# classix.net
KiCad netlist of a schematic drawn in EAGLE
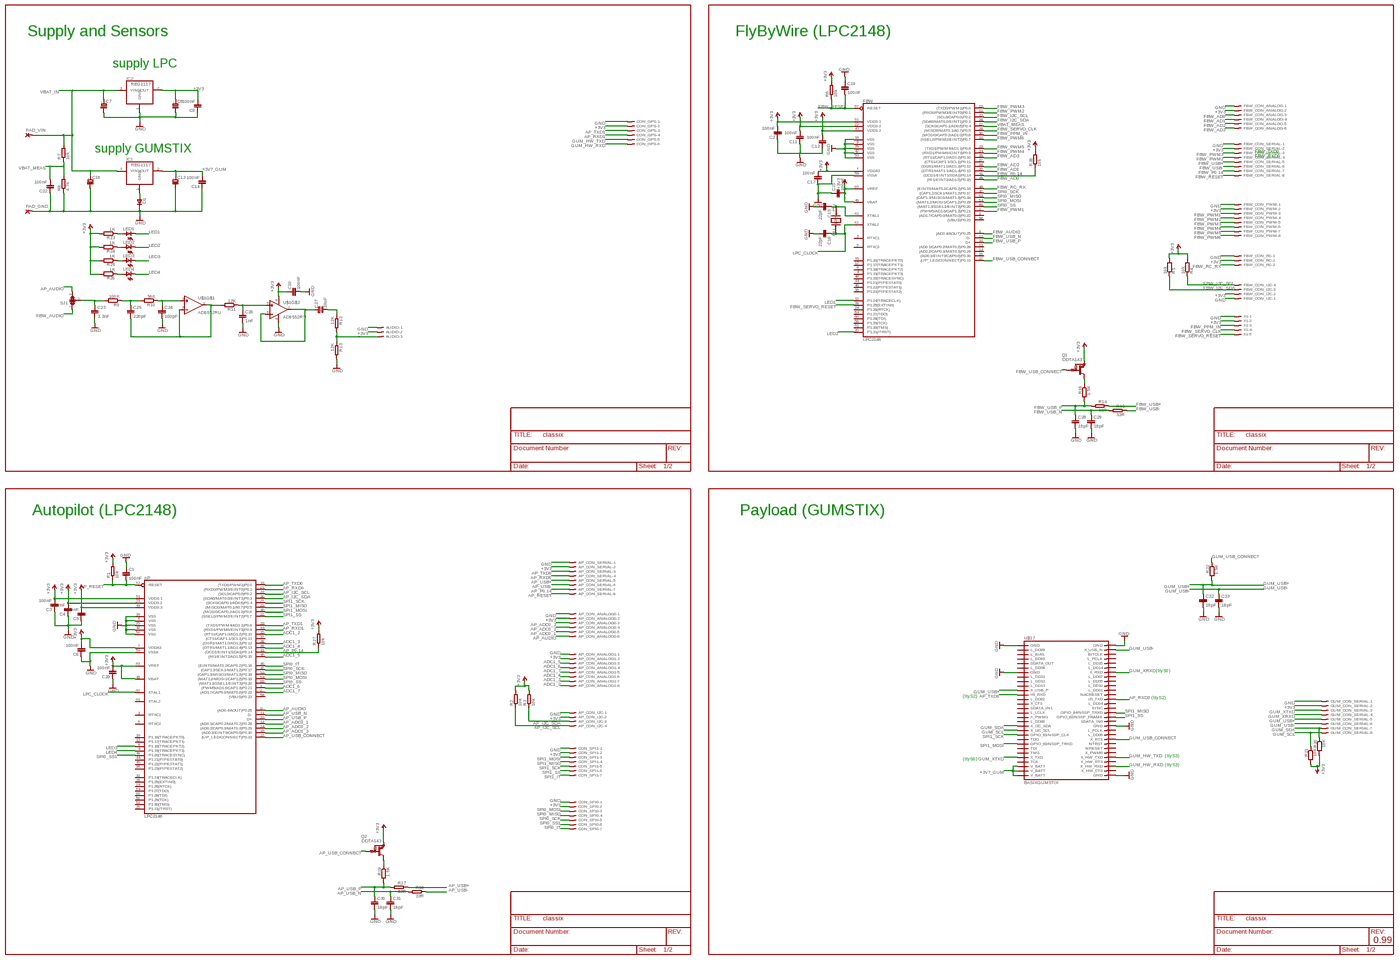
[diagram p0: schematic, sheet 1, overview]
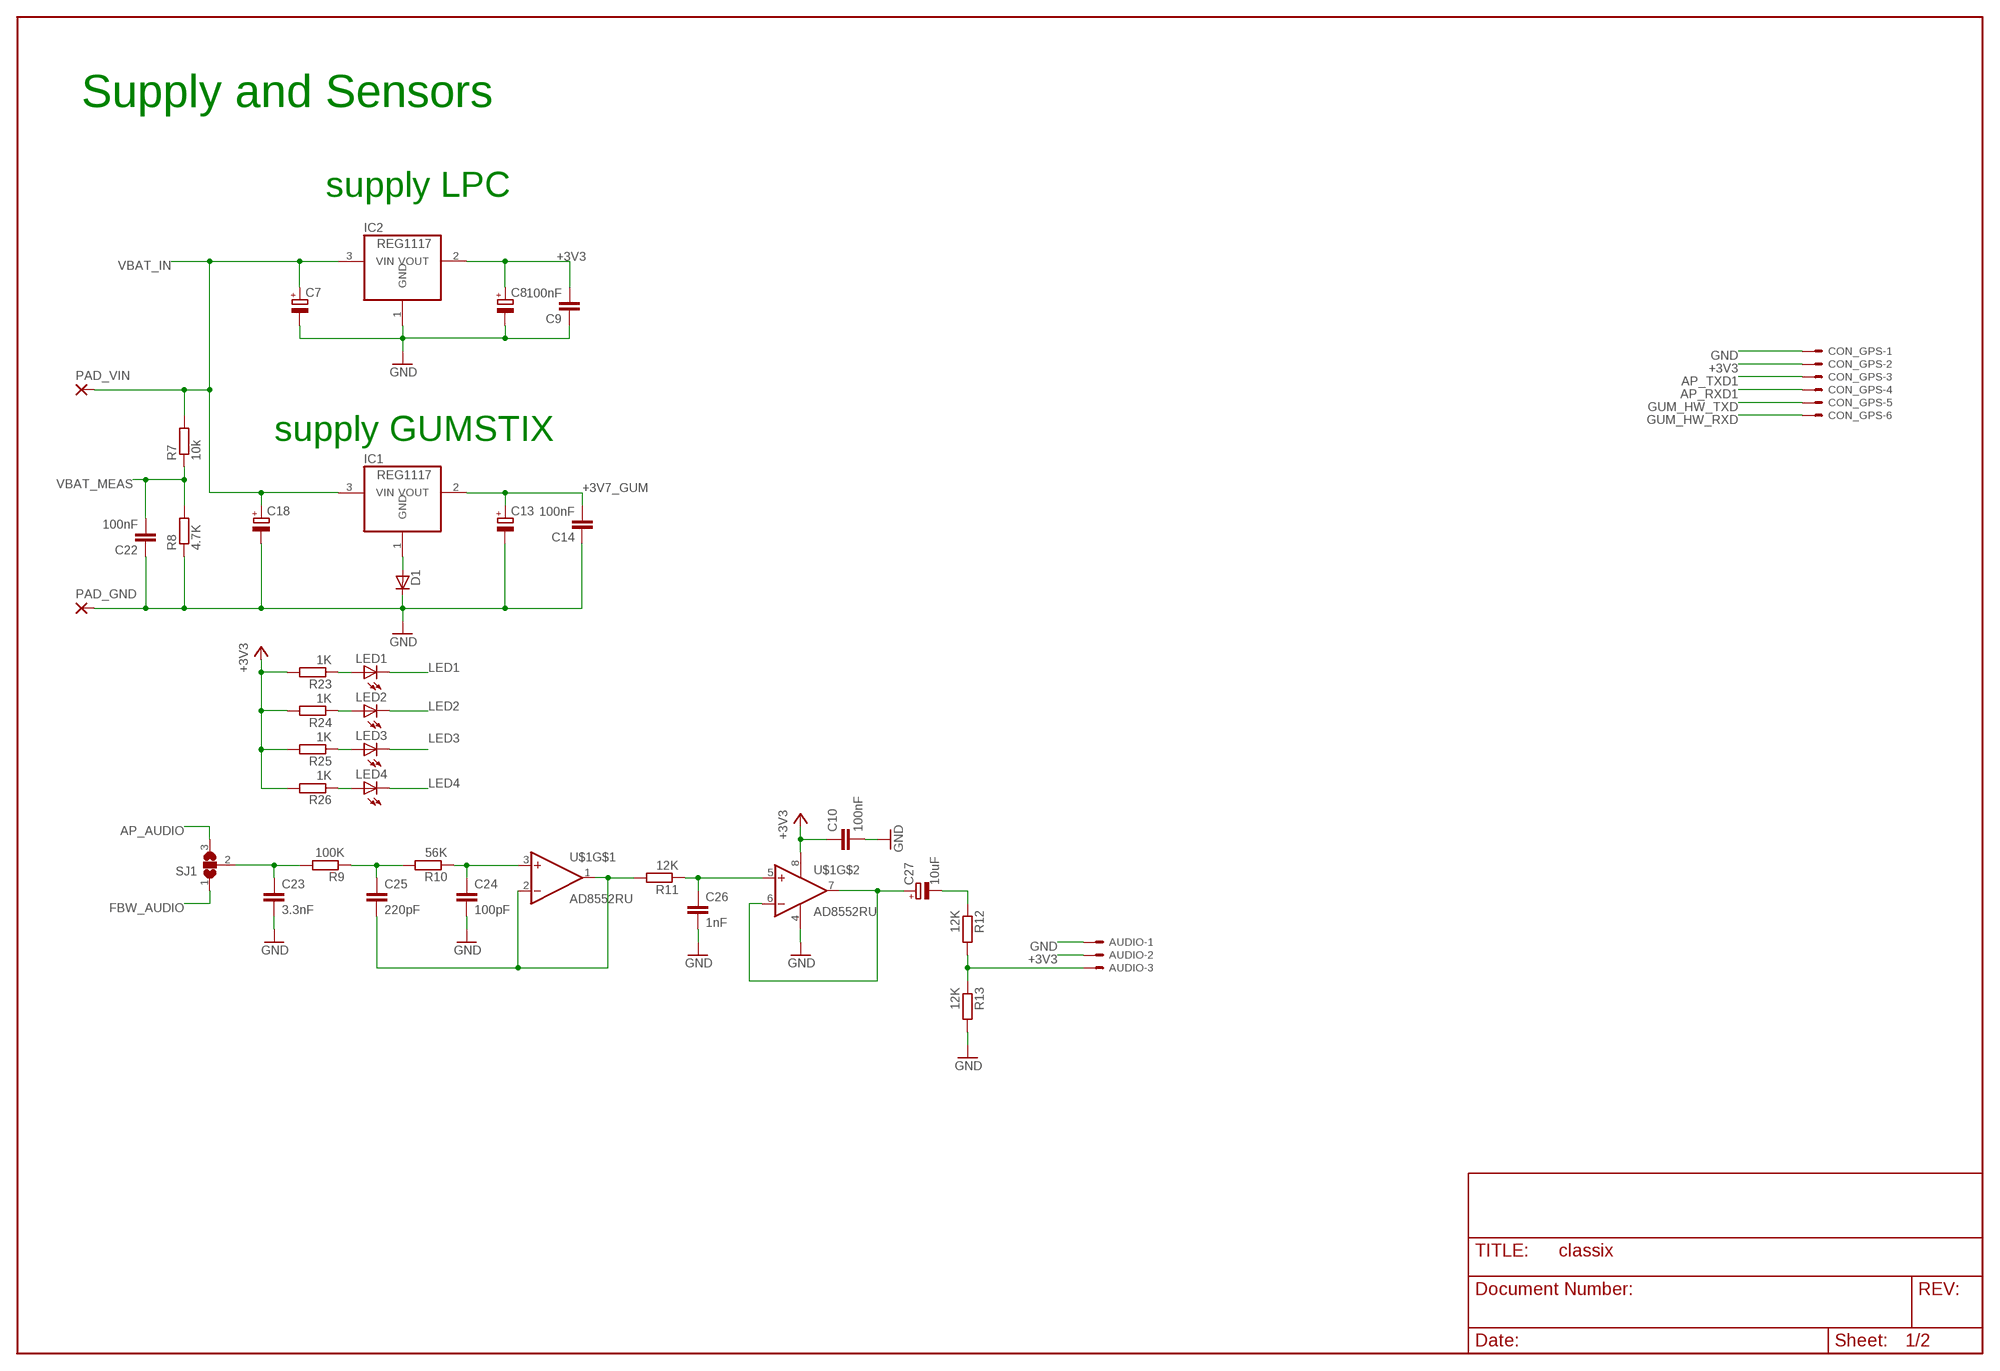
[diagram p1: schematic, sheet 1, part 1 of 4]
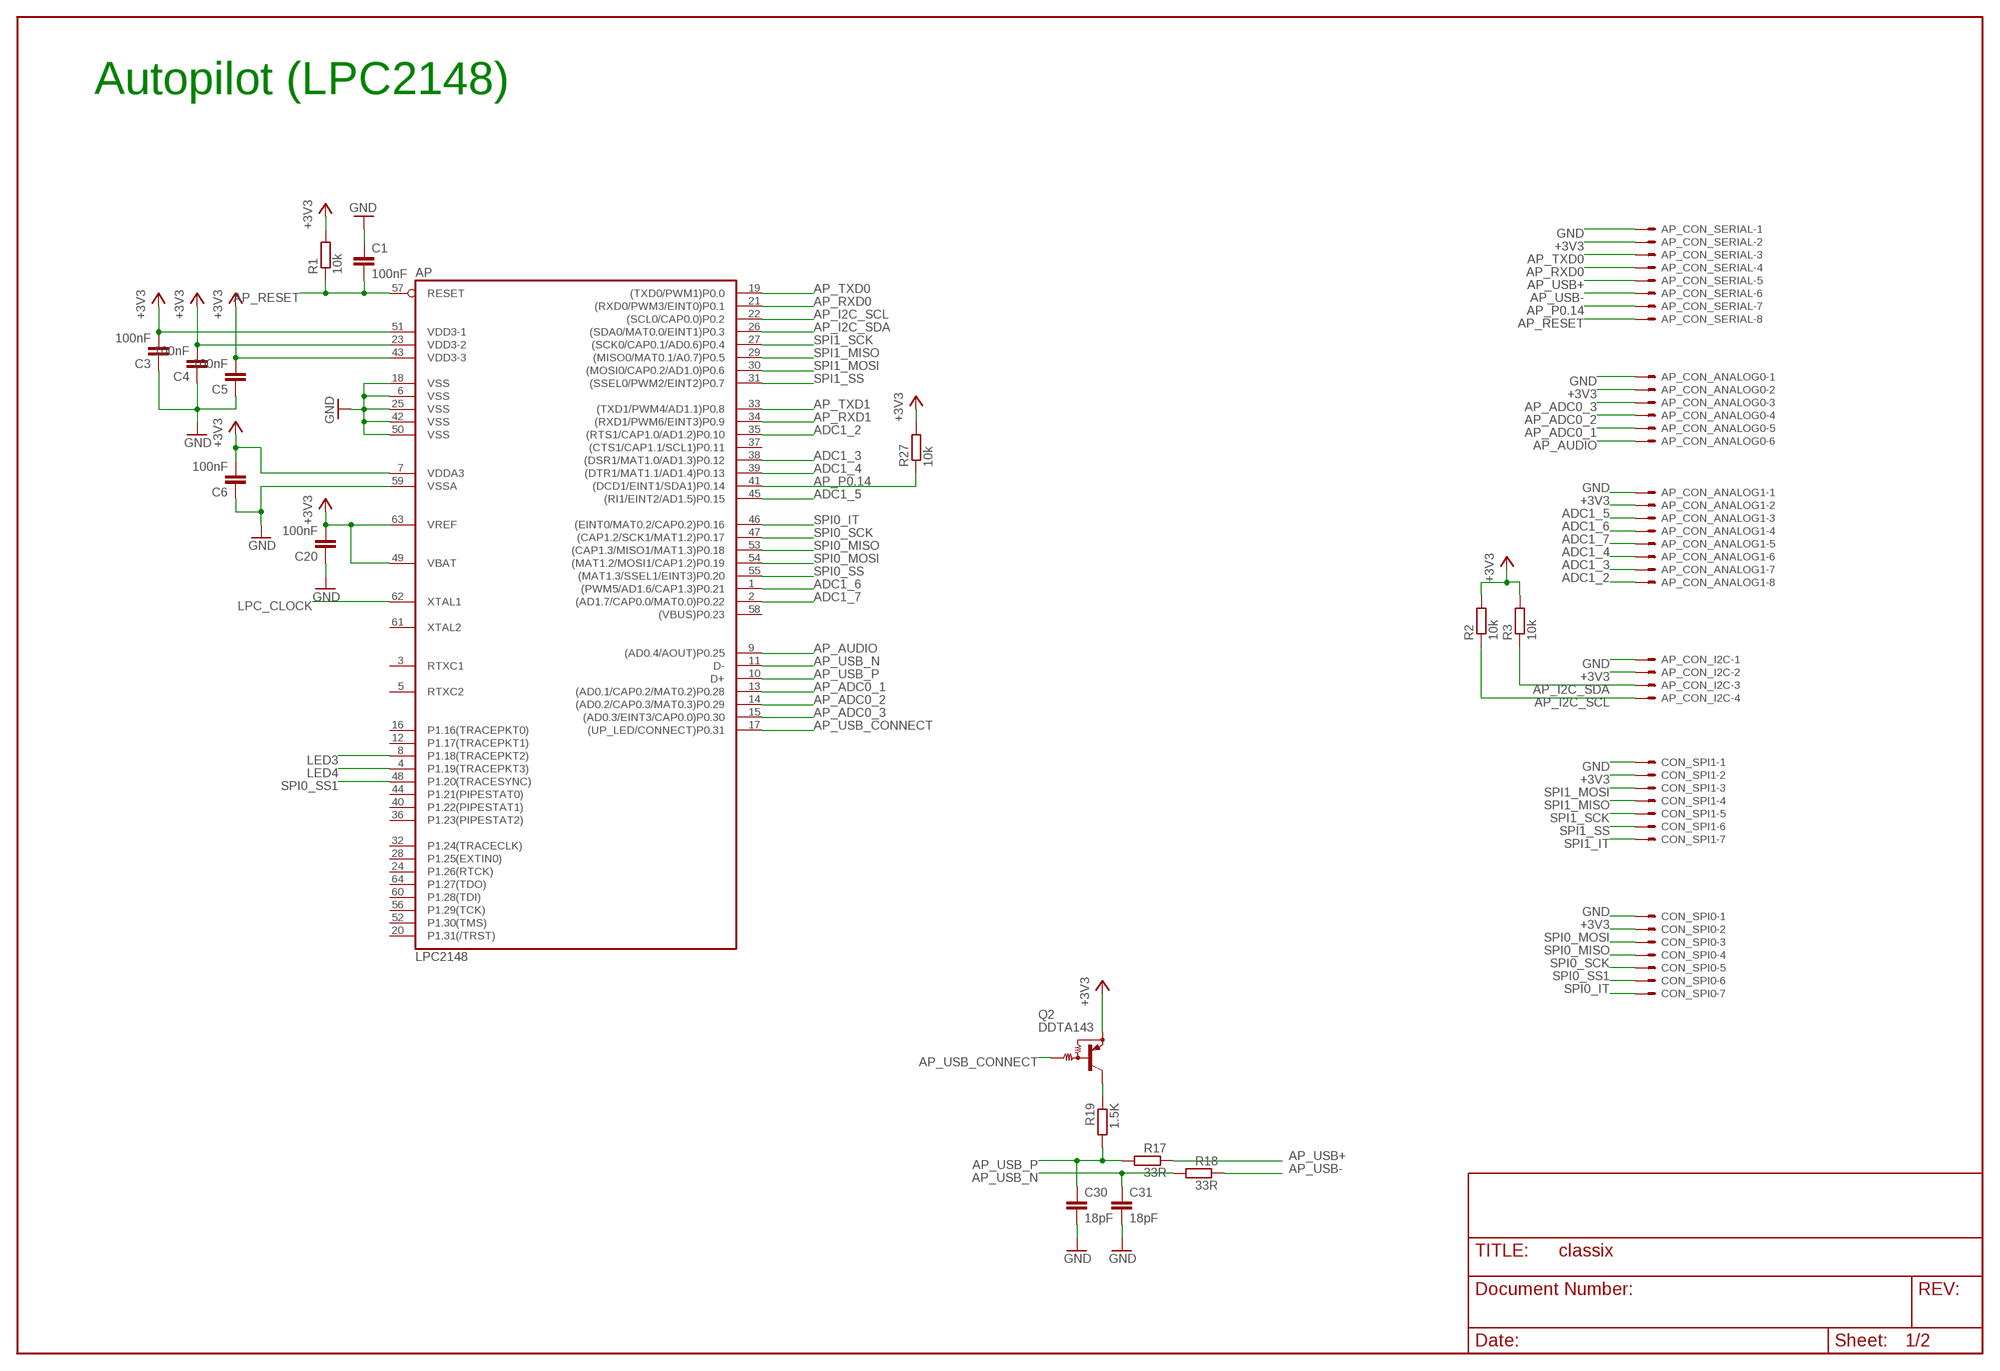
[diagram p2: schematic, sheet 1, part 2 of 4]
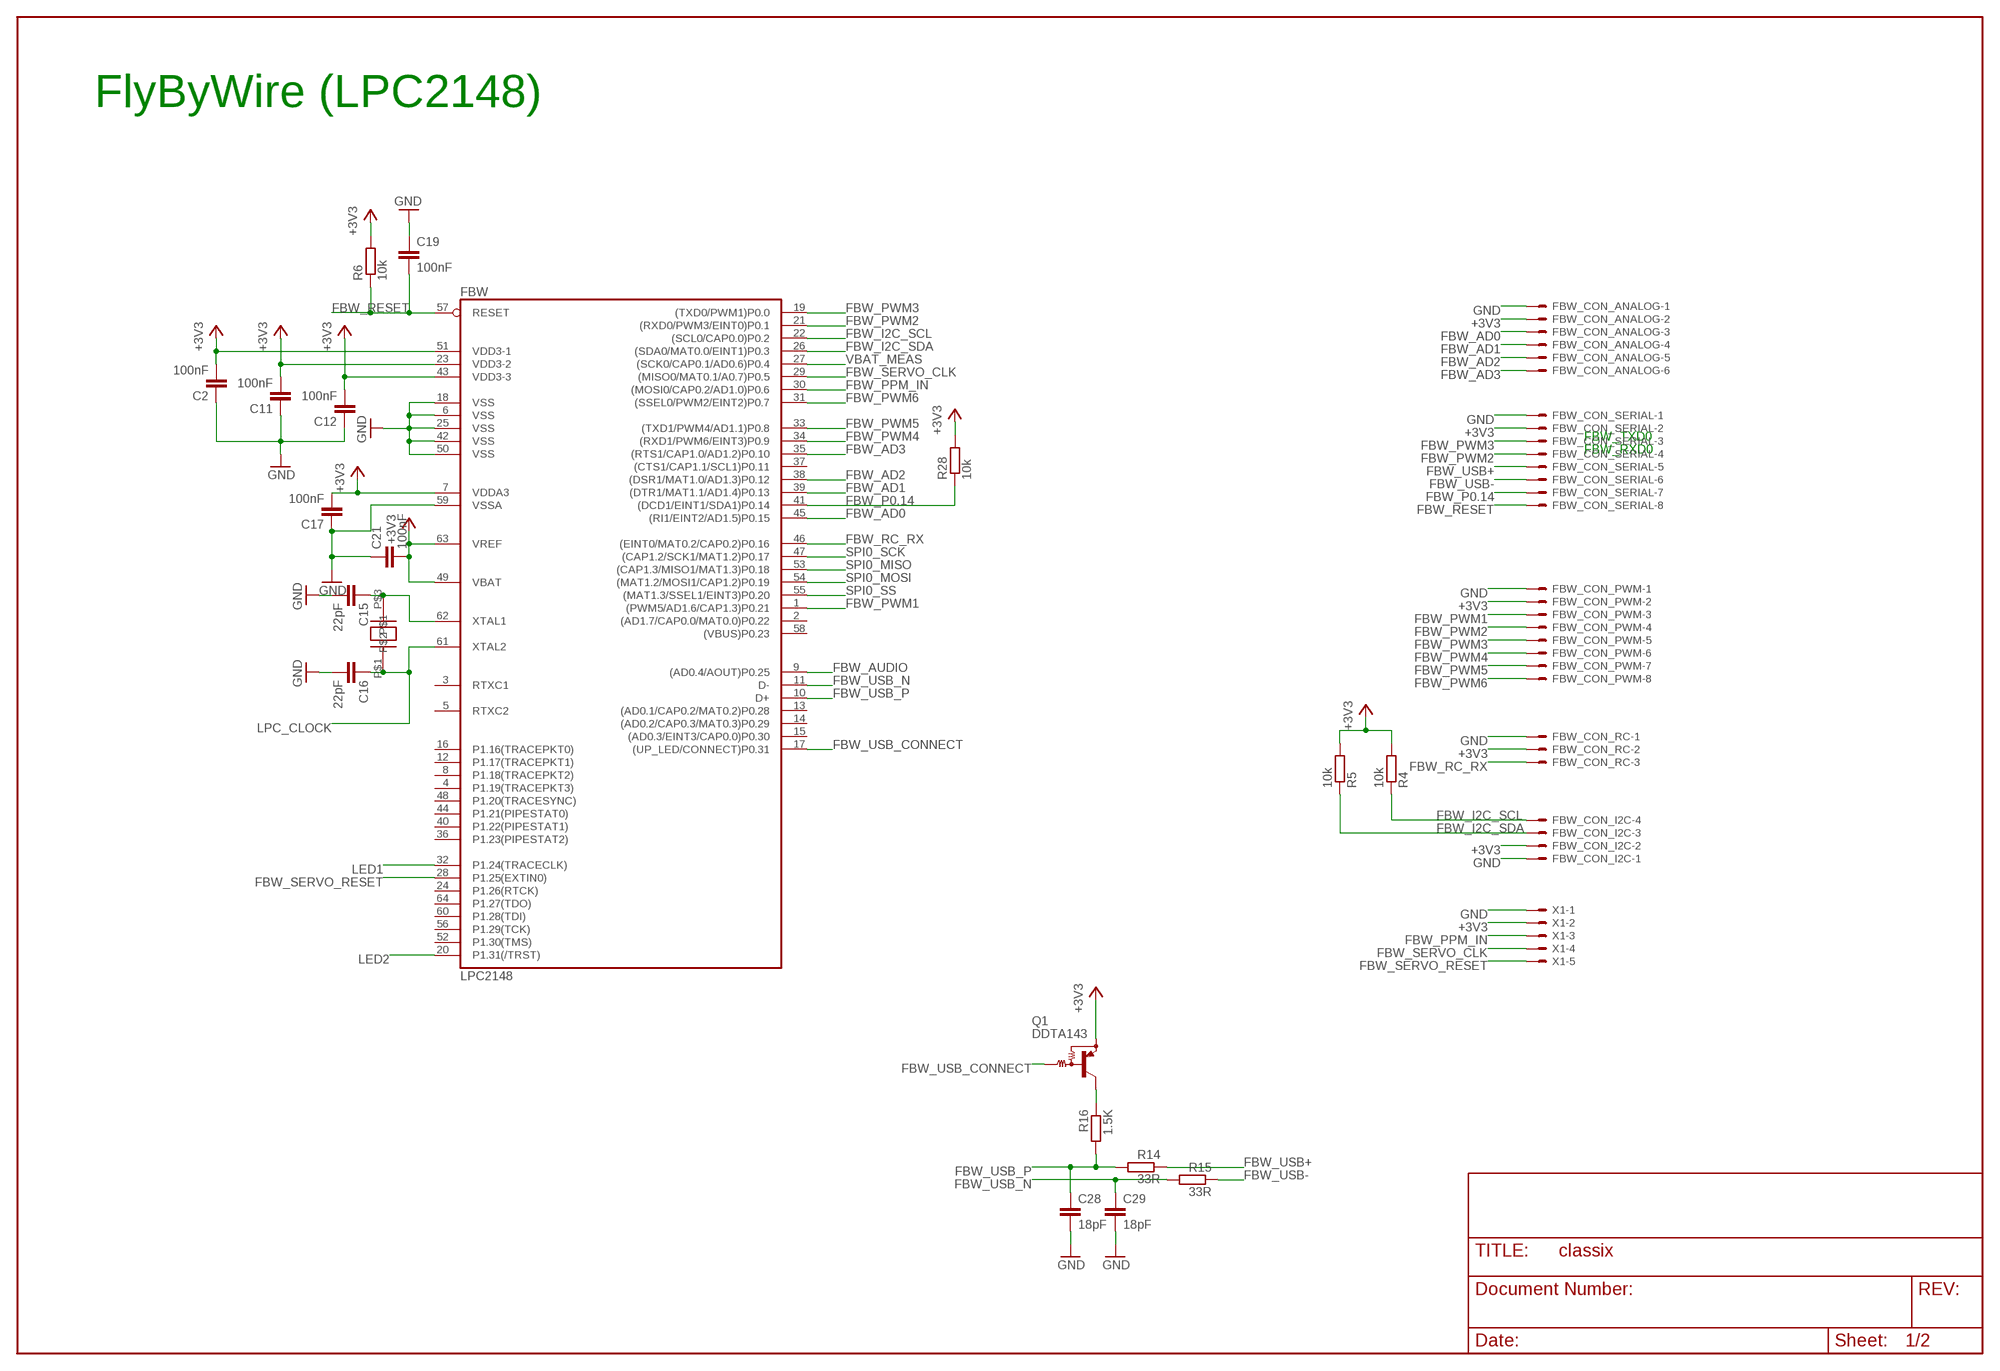
[diagram p3: schematic, sheet 1, part 3 of 4]
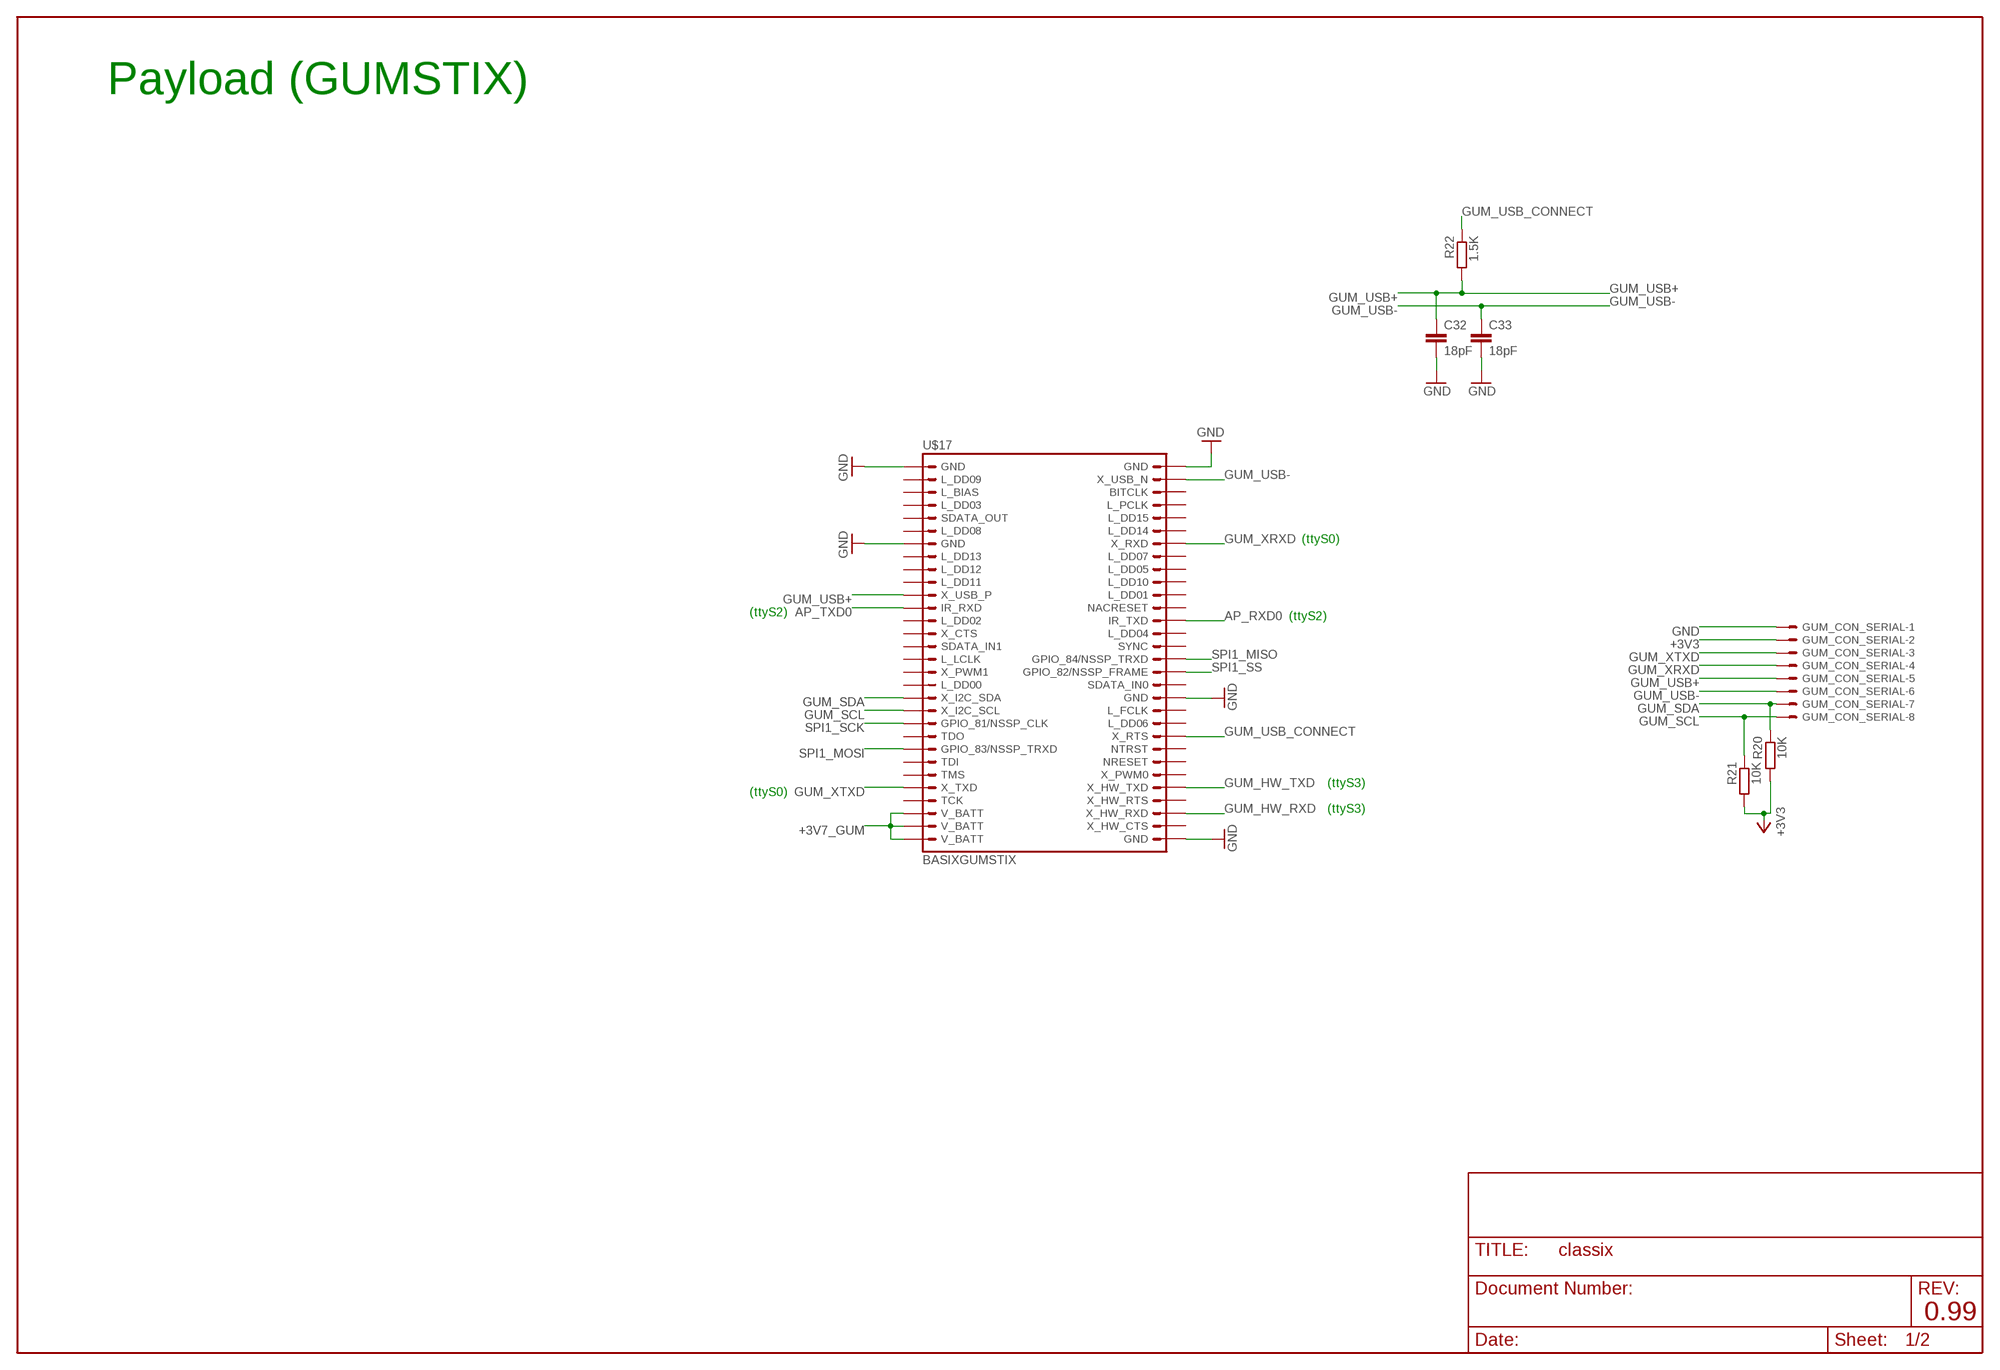
[diagram p4: schematic, sheet 1, part 4 of 4]

(export (version "E")
  (design (tool "Eeschema 10.0.6"))
  (components
    (comp (ref "AP")
      (value "LPC2148")
      (footprint "eagle-import:SQFP-S-10X10-64")
      (libsource (lib "eagle-import") (part "LPC2148"))
    )
    (comp (ref "AP_CON_ANALOG0")
      (value "53047-06")
      (footprint "eagle-import:53047-06")
      (libsource (lib "eagle-import") (part "53?-06047"))
    )
    (comp (ref "AP_CON_ANALOG1")
      (value "53047-08")
      (footprint "eagle-import:53047-08")
      (libsource (lib "eagle-import") (part "53?-08047"))
    )
    (comp (ref "AP_CON_I2C")
      (value "53047-04")
      (footprint "eagle-import:53047-04")
      (libsource (lib "eagle-import") (part "53?-04047"))
    )
    (comp (ref "AP_CON_SERIAL")
      (value "53047-08")
      (footprint "eagle-import:53047-08")
      (libsource (lib "eagle-import") (part "53?-08047"))
    )
    (comp (ref "AUDIO")
      (value "53047-03")
      (footprint "eagle-import:53047-03")
      (libsource (lib "eagle-import") (part "53?-03047"))
    )
    (comp (ref "C1")
      (value "100nF")
      (footprint "eagle-import:C0603")
      (libsource (lib "eagle-import") (part "C-EUC0603"))
    )
    (comp (ref "C2")
      (value "100nF")
      (footprint "eagle-import:C0603")
      (libsource (lib "eagle-import") (part "C-EUC0603"))
    )
    (comp (ref "C3")
      (value "100nF")
      (footprint "eagle-import:C0603")
      (libsource (lib "eagle-import") (part "C-EUC0603"))
    )
    (comp (ref "C4")
      (value "100nF")
      (footprint "eagle-import:C0603")
      (libsource (lib "eagle-import") (part "C-EUC0603"))
    )
    (comp (ref "C5")
      (value "100nF")
      (footprint "eagle-import:C0603")
      (libsource (lib "eagle-import") (part "C-EUC0603"))
    )
    (comp (ref "C6")
      (value "100nF")
      (footprint "eagle-import:C0603")
      (libsource (lib "eagle-import") (part "C-EUC0603"))
    )
    (comp (ref "C7")
      (value "CPOL-EUA/3216-18R")
      (footprint "eagle-import:A_3216-18R")
      (libsource (lib "eagle-import") (part "CPOL-EUA/3216-18R"))
    )
    (comp (ref "C8")
      (value "CPOL-EUB/3528-21R")
      (footprint "eagle-import:B_3528-21R")
      (libsource (lib "eagle-import") (part "CPOL-EUB/3528-21R"))
    )
    (comp (ref "C9")
      (value "100nF")
      (footprint "eagle-import:C0603")
      (libsource (lib "eagle-import") (part "C-EUC0603"))
    )
    (comp (ref "C10")
      (value "100nF")
      (footprint "eagle-import:C0603")
      (libsource (lib "eagle-import") (part "C-EUC0603"))
    )
    (comp (ref "C11")
      (value "100nF")
      (footprint "eagle-import:C0603")
      (libsource (lib "eagle-import") (part "C-EUC0603"))
    )
    (comp (ref "C12")
      (value "100nF")
      (footprint "eagle-import:C0603")
      (libsource (lib "eagle-import") (part "C-EUC0603"))
    )
    (comp (ref "C13")
      (value "CPOL-EUB/3528-21R")
      (footprint "eagle-import:B_3528-21R")
      (libsource (lib "eagle-import") (part "CPOL-EUB/3528-21R"))
    )
    (comp (ref "C14")
      (value "100nF")
      (footprint "eagle-import:C0603")
      (libsource (lib "eagle-import") (part "C-EUC0603"))
    )
    (comp (ref "C15")
      (value "22pF")
      (footprint "eagle-import:C0603")
      (libsource (lib "eagle-import") (part "C-EUC0603"))
    )
    (comp (ref "C16")
      (value "22pF")
      (footprint "eagle-import:C0603")
      (libsource (lib "eagle-import") (part "C-EUC0603"))
    )
    (comp (ref "C17")
      (value "100nF")
      (footprint "eagle-import:C0603")
      (libsource (lib "eagle-import") (part "C-EUC0603"))
    )
    (comp (ref "C18")
      (value "CPOL-EUA/3216-18R")
      (footprint "eagle-import:A_3216-18R")
      (libsource (lib "eagle-import") (part "CPOL-EUA/3216-18R"))
    )
    (comp (ref "C19")
      (value "100nF")
      (footprint "eagle-import:C0603")
      (libsource (lib "eagle-import") (part "C-EUC0603"))
    )
    (comp (ref "C20")
      (value "100nF")
      (footprint "eagle-import:C0603")
      (libsource (lib "eagle-import") (part "C-EUC0603"))
    )
    (comp (ref "C21")
      (value "100nF")
      (footprint "eagle-import:C0603")
      (libsource (lib "eagle-import") (part "C-EUC0603"))
    )
    (comp (ref "C22")
      (value "100nF")
      (footprint "eagle-import:C0603")
      (libsource (lib "eagle-import") (part "C-EUC0603"))
    )
    (comp (ref "C23")
      (value "3.3nF")
      (footprint "eagle-import:C0603")
      (libsource (lib "eagle-import") (part "C-EUC0603"))
    )
    (comp (ref "C24")
      (value "100pF")
      (footprint "eagle-import:C0603")
      (libsource (lib "eagle-import") (part "C-EUC0603"))
    )
    (comp (ref "C25")
      (value "220pF")
      (footprint "eagle-import:C0603")
      (libsource (lib "eagle-import") (part "C-EUC0603"))
    )
    (comp (ref "C26")
      (value "1nF")
      (footprint "eagle-import:C0603")
      (libsource (lib "eagle-import") (part "C-EUC0603"))
    )
    (comp (ref "C27")
      (value "10uF")
      (footprint "eagle-import:A_3216-18R")
      (libsource (lib "eagle-import") (part "CPOL-EUA/3216-18R"))
    )
    (comp (ref "C28")
      (value "18pF")
      (footprint "eagle-import:C0603")
      (libsource (lib "eagle-import") (part "C-EUC0603"))
    )
    (comp (ref "C29")
      (value "18pF")
      (footprint "eagle-import:C0603")
      (libsource (lib "eagle-import") (part "C-EUC0603"))
    )
    (comp (ref "C30")
      (value "18pF")
      (footprint "eagle-import:C0603")
      (libsource (lib "eagle-import") (part "C-EUC0603"))
    )
    (comp (ref "C31")
      (value "18pF")
      (footprint "eagle-import:C0603")
      (libsource (lib "eagle-import") (part "C-EUC0603"))
    )
    (comp (ref "C32")
      (value "18pF")
      (footprint "eagle-import:C0603")
      (libsource (lib "eagle-import") (part "C-EUC0603"))
    )
    (comp (ref "C33")
      (value "18pF")
      (footprint "eagle-import:C0603")
      (libsource (lib "eagle-import") (part "C-EUC0603"))
    )
    (comp (ref "CON_GPS")
      (value "53047-06")
      (footprint "eagle-import:53047-06")
      (libsource (lib "eagle-import") (part "53?-06047"))
    )
    (comp (ref "CON_SPI0")
      (value "53047-07")
      (footprint "eagle-import:53047-07")
      (libsource (lib "eagle-import") (part "53?-07047"))
    )
    (comp (ref "CON_SPI1")
      (value "53047-07")
      (footprint "eagle-import:53047-07")
      (libsource (lib "eagle-import") (part "53?-07047"))
    )
    (comp (ref "D1")
      (value "D-SOD-80")
      (footprint "eagle-import:SOD80")
      (libsource (lib "eagle-import") (part "D-SOD-80"))
    )
    (comp (ref "FBW")
      (value "LPC2148")
      (footprint "eagle-import:SQFP-S-10X10-64")
      (libsource (lib "eagle-import") (part "LPC2148"))
    )
    (comp (ref "FBW_CON_ANALOG")
      (value "53047-06")
      (footprint "eagle-import:53047-06")
      (libsource (lib "eagle-import") (part "53?-06047"))
    )
    (comp (ref "FBW_CON_I2C")
      (value "53047-04")
      (footprint "eagle-import:53047-04")
      (libsource (lib "eagle-import") (part "53?-04047"))
    )
    (comp (ref "FBW_CON_PWM")
      (value "53047-08")
      (footprint "eagle-import:53047-08")
      (libsource (lib "eagle-import") (part "53?-08047"))
    )
    (comp (ref "FBW_CON_RC")
      (value "53047-03")
      (footprint "eagle-import:53047-03")
      (libsource (lib "eagle-import") (part "53?-03047"))
    )
    (comp (ref "FBW_CON_SERIAL")
      (value "53047-08")
      (footprint "eagle-import:53047-08")
      (libsource (lib "eagle-import") (part "53?-08047"))
    )
    (comp (ref "GUM_CON_SERIAL")
      (value "53047-08")
      (footprint "eagle-import:53047-08")
      (libsource (lib "eagle-import") (part "53?-08047"))
    )
    (comp (ref "IC1")
      (value "REG1117")
      (footprint "eagle-import:SOT223")
      (libsource (lib "eagle-import") (part "REG1117"))
    )
    (comp (ref "IC2")
      (value "REG1117")
      (footprint "eagle-import:SOT223")
      (libsource (lib "eagle-import") (part "REG1117"))
    )
    (comp (ref "LED1")
      (value "LEDCHIP-LED0805")
      (footprint "eagle-import:CHIP-LED0805")
      (libsource (lib "eagle-import") (part "LEDCHIP-LED0805"))
    )
    (comp (ref "LED2")
      (value "LEDCHIP-LED0805")
      (footprint "eagle-import:CHIP-LED0805")
      (libsource (lib "eagle-import") (part "LEDCHIP-LED0805"))
    )
    (comp (ref "LED3")
      (value "LEDCHIP-LED0805")
      (footprint "eagle-import:CHIP-LED0805")
      (libsource (lib "eagle-import") (part "LEDCHIP-LED0805"))
    )
    (comp (ref "LED4")
      (value "LEDCHIP-LED0805")
      (footprint "eagle-import:CHIP-LED0805")
      (libsource (lib "eagle-import") (part "LEDCHIP-LED0805"))
    )
    (comp (ref "PAD_GND")
      (value "SMD5")
      (footprint "eagle-import:SMD5")
      (libsource (lib "eagle-import") (part "SMD5"))
    )
    (comp (ref "PAD_VIN")
      (value "SMD5")
      (footprint "eagle-import:SMD5")
      (libsource (lib "eagle-import") (part "SMD5"))
    )
    (comp (ref "Q1")
      (value "DDTA143")
      (footprint "eagle-import:SC59-BEC")
      (libsource (lib "eagle-import") (part "MUN2111T1"))
    )
    (comp (ref "Q2")
      (value "DDTA143")
      (footprint "eagle-import:SC59-BEC")
      (libsource (lib "eagle-import") (part "MUN2111T1"))
    )
    (comp (ref "R1")
      (value "10k")
      (footprint "eagle-import:R0603")
      (libsource (lib "eagle-import") (part "R-EU_R0603"))
    )
    (comp (ref "R2")
      (value "10k")
      (footprint "eagle-import:R0603")
      (libsource (lib "eagle-import") (part "R-EU_R0603"))
    )
    (comp (ref "R3")
      (value "10k")
      (footprint "eagle-import:R0603")
      (libsource (lib "eagle-import") (part "R-EU_R0603"))
    )
    (comp (ref "R4")
      (value "10k")
      (footprint "eagle-import:R0603")
      (libsource (lib "eagle-import") (part "R-EU_R0603"))
    )
    (comp (ref "R5")
      (value "10k")
      (footprint "eagle-import:R0603")
      (libsource (lib "eagle-import") (part "R-EU_R0603"))
    )
    (comp (ref "R6")
      (value "10k")
      (footprint "eagle-import:R0603")
      (libsource (lib "eagle-import") (part "R-EU_R0603"))
    )
    (comp (ref "R7")
      (value "10k")
      (footprint "eagle-import:R0603")
      (libsource (lib "eagle-import") (part "R-EU_R0603"))
    )
    (comp (ref "R8")
      (value "4.7K")
      (footprint "eagle-import:R0603")
      (libsource (lib "eagle-import") (part "R-EU_R0603"))
    )
    (comp (ref "R9")
      (value "100K")
      (footprint "eagle-import:R0603")
      (libsource (lib "eagle-import") (part "R-EU_R0603"))
    )
    (comp (ref "R10")
      (value "56K")
      (footprint "eagle-import:R0603")
      (libsource (lib "eagle-import") (part "R-EU_R0603"))
    )
    (comp (ref "R11")
      (value "12K")
      (footprint "eagle-import:R0603")
      (libsource (lib "eagle-import") (part "R-EU_R0603"))
    )
    (comp (ref "R12")
      (value "12K")
      (footprint "eagle-import:R0603")
      (libsource (lib "eagle-import") (part "R-EU_R0603"))
    )
    (comp (ref "R13")
      (value "12K")
      (footprint "eagle-import:R0603")
      (libsource (lib "eagle-import") (part "R-EU_R0603"))
    )
    (comp (ref "R14")
      (value "33R")
      (footprint "eagle-import:R0603")
      (libsource (lib "eagle-import") (part "R-EU_R0603"))
    )
    (comp (ref "R15")
      (value "33R")
      (footprint "eagle-import:R0603")
      (libsource (lib "eagle-import") (part "R-EU_R0603"))
    )
    (comp (ref "R16")
      (value "1.5K")
      (footprint "eagle-import:R0603")
      (libsource (lib "eagle-import") (part "R-EU_R0603"))
    )
    (comp (ref "R17")
      (value "33R")
      (footprint "eagle-import:R0603")
      (libsource (lib "eagle-import") (part "R-EU_R0603"))
    )
    (comp (ref "R18")
      (value "33R")
      (footprint "eagle-import:R0603")
      (libsource (lib "eagle-import") (part "R-EU_R0603"))
    )
    (comp (ref "R19")
      (value "1.5K")
      (footprint "eagle-import:R0603")
      (libsource (lib "eagle-import") (part "R-EU_R0603"))
    )
    (comp (ref "R20")
      (value "10K")
      (footprint "eagle-import:R0603")
      (libsource (lib "eagle-import") (part "R-EU_R0603"))
    )
    (comp (ref "R21")
      (value "10K")
      (footprint "eagle-import:R0603")
      (libsource (lib "eagle-import") (part "R-EU_R0603"))
    )
    (comp (ref "R22")
      (value "1.5K")
      (footprint "eagle-import:R0603")
      (libsource (lib "eagle-import") (part "R-EU_R0603"))
    )
    (comp (ref "R23")
      (value "1K")
      (footprint "eagle-import:R0603")
      (libsource (lib "eagle-import") (part "R-EU_R0603"))
    )
    (comp (ref "R24")
      (value "1K")
      (footprint "eagle-import:R0603")
      (libsource (lib "eagle-import") (part "R-EU_R0603"))
    )
    (comp (ref "R25")
      (value "1K")
      (footprint "eagle-import:R0603")
      (libsource (lib "eagle-import") (part "R-EU_R0603"))
    )
    (comp (ref "R26")
      (value "1K")
      (footprint "eagle-import:R0603")
      (libsource (lib "eagle-import") (part "R-EU_R0603"))
    )
    (comp (ref "R27")
      (value "10k")
      (footprint "eagle-import:R0603")
      (libsource (lib "eagle-import") (part "R-EU_R0603"))
    )
    (comp (ref "R28")
      (value "10k")
      (footprint "eagle-import:R0603")
      (libsource (lib "eagle-import") (part "R-EU_R0603"))
    )
    (comp (ref "SJ1")
      (value "SJ2W")
      (footprint "eagle-import:SJ_2")
      (libsource (lib "eagle-import") (part "SJ2W"))
    )
    (comp (ref "U$1")
      (value "AD8552RU")
      (footprint "eagle-import:TSSOP8")
      (libsource (lib "eagle-import") (part "AD8552RU"))
    )
    (comp (ref "U$17")
      (value "BASIXGUMSTIX")
      (footprint "eagle-import:GUMDF12")
      (libsource (lib "eagle-import") (part "BASIXGUMSTIX"))
    )
    (comp (ref "U$20")
      (value "CRYSTAL_CTS")
      (footprint "eagle-import:CTS_CRYSTAL")
      (libsource (lib "eagle-import") (part "CRYSTAL_CTS"))
    )
    (comp (ref "X1")
      (value "53047-05")
      (footprint "eagle-import:53047-05")
      (libsource (lib "eagle-import") (part "53?-05047"))
    )
  )
  (nets
    (net (code "1") (name "+3V3") (class "Default")
      (node (ref "AP") (pin "23") (pinfunction "VDD3-2_23") (pintype "power_in"))
      (node (ref "AP") (pin "43") (pinfunction "VDD3-3_43") (pintype "power_in"))
      (node (ref "AP") (pin "49") (pinfunction "VBAT_49") (pintype "power_in"))
      (node (ref "AP") (pin "51") (pinfunction "VDD3-1_51") (pintype "power_in"))
      (node (ref "AP") (pin "63") (pinfunction "VREF_63") (pintype "input"))
      (node (ref "AP") (pin "7") (pinfunction "VDDA3_7") (pintype "power_in"))
      (node (ref "AP_CON_ANALOG0") (pin "2") (pinfunction "S_2") (pintype "passive"))
      (node (ref "AP_CON_ANALOG1") (pin "2") (pinfunction "S_2") (pintype "passive"))
      (node (ref "AP_CON_I2C") (pin "2") (pinfunction "S_2") (pintype "passive"))
      (node (ref "AP_CON_SERIAL") (pin "2") (pinfunction "S_2") (pintype "passive"))
      (node (ref "AUDIO") (pin "2") (pinfunction "S_2") (pintype "passive"))
      (node (ref "C10") (pin "1") (pinfunction "1_1") (pintype "passive"))
      (node (ref "C11") (pin "2") (pinfunction "2_2") (pintype "passive"))
      (node (ref "C12") (pin "2") (pinfunction "2_2") (pintype "passive"))
      (node (ref "C17") (pin "2") (pinfunction "2_2") (pintype "passive"))
      (node (ref "C2") (pin "2") (pinfunction "2_2") (pintype "passive"))
      (node (ref "C20") (pin "2") (pinfunction "2_2") (pintype "passive"))
      (node (ref "C21") (pin "2") (pinfunction "2_2") (pintype "passive"))
      (node (ref "C3") (pin "2") (pinfunction "2_2") (pintype "passive"))
      (node (ref "C4") (pin "2") (pinfunction "2_2") (pintype "passive"))
      (node (ref "C5") (pin "2") (pinfunction "2_2") (pintype "passive"))
      (node (ref "C6") (pin "2") (pinfunction "2_2") (pintype "passive"))
      (node (ref "C8") (pin "+") (pinfunction "+_+") (pintype "passive"))
      (node (ref "C9") (pin "2") (pinfunction "2_2") (pintype "passive"))
      (node (ref "CON_GPS") (pin "2") (pinfunction "S_2") (pintype "passive"))
      (node (ref "CON_SPI0") (pin "2") (pinfunction "S_2") (pintype "passive"))
      (node (ref "CON_SPI1") (pin "2") (pinfunction "S_2") (pintype "passive"))
      (node (ref "FBW") (pin "23") (pinfunction "VDD3-2_23") (pintype "power_in"))
      (node (ref "FBW") (pin "43") (pinfunction "VDD3-3_43") (pintype "power_in"))
      (node (ref "FBW") (pin "49") (pinfunction "VBAT_49") (pintype "power_in"))
      (node (ref "FBW") (pin "51") (pinfunction "VDD3-1_51") (pintype "power_in"))
      (node (ref "FBW") (pin "63") (pinfunction "VREF_63") (pintype "input"))
      (node (ref "FBW") (pin "7") (pinfunction "VDDA3_7") (pintype "power_in"))
      (node (ref "FBW_CON_ANALOG") (pin "2") (pinfunction "S_2") (pintype "passive"))
      (node (ref "FBW_CON_I2C") (pin "2") (pinfunction "S_2") (pintype "passive"))
      (node (ref "FBW_CON_PWM") (pin "2") (pinfunction "S_2") (pintype "passive"))
      (node (ref "FBW_CON_RC") (pin "2") (pinfunction "S_2") (pintype "passive"))
      (node (ref "FBW_CON_SERIAL") (pin "2") (pinfunction "S_2") (pintype "passive"))
      (node (ref "GUM_CON_SERIAL") (pin "2") (pinfunction "S_2") (pintype "passive"))
      (node (ref "IC2") (pin "2") (pinfunction "VOUT_2") (pintype "output"))
      (node (ref "Q1") (pin "E") (pinfunction "E_E") (pintype "passive"))
      (node (ref "Q2") (pin "E") (pinfunction "E_E") (pintype "passive"))
      (node (ref "R1") (pin "2") (pinfunction "2_2") (pintype "passive"))
      (node (ref "R2") (pin "2") (pinfunction "2_2") (pintype "passive"))
      (node (ref "R20") (pin "2") (pinfunction "2_2") (pintype "passive"))
      (node (ref "R21") (pin "2") (pinfunction "2_2") (pintype "passive"))
      (node (ref "R23") (pin "2") (pinfunction "2_2") (pintype "passive"))
      (node (ref "R24") (pin "2") (pinfunction "2_2") (pintype "passive"))
      (node (ref "R25") (pin "2") (pinfunction "2_2") (pintype "passive"))
      (node (ref "R26") (pin "2") (pinfunction "2_2") (pintype "passive"))
      (node (ref "R27") (pin "2") (pinfunction "2_2") (pintype "passive"))
      (node (ref "R28") (pin "2") (pinfunction "2_2") (pintype "passive"))
      (node (ref "R3") (pin "2") (pinfunction "2_2") (pintype "passive"))
      (node (ref "R4") (pin "2") (pinfunction "2_2") (pintype "passive"))
      (node (ref "R5") (pin "2") (pinfunction "2_2") (pintype "passive"))
      (node (ref "R6") (pin "2") (pinfunction "2_2") (pintype "passive"))
      (node (ref "U$1") (pin "8") (pinfunction "V+_8") (pintype "power_in"))
      (node (ref "X1") (pin "2") (pinfunction "S_2") (pintype "passive"))
    )
    (net (code "2") (name "+3V7_GUM") (class "Default")
      (node (ref "C13") (pin "+") (pinfunction "+_+") (pintype "passive"))
      (node (ref "C14") (pin "2") (pinfunction "2_2") (pintype "passive"))
      (node (ref "IC1") (pin "2") (pinfunction "VOUT_2") (pintype "output"))
      (node (ref "U$17") (pin "28") (pinfunction "V_BATT_28") (pintype "power_in"))
      (node (ref "U$17") (pin "29") (pinfunction "V_BATT_29") (pintype "power_in"))
      (node (ref "U$17") (pin "30") (pinfunction "V_BATT_30") (pintype "power_in"))
    )
    (net (code "3") (name "ADC1_2") (class "Default")
      (node (ref "AP") (pin "35") (pinfunction "(RTS1/CAP1.0/AD1.2)P0.10_35") (pintype "bidirectional"))
      (node (ref "AP_CON_ANALOG1") (pin "8") (pinfunction "S_8") (pintype "passive"))
    )
    (net (code "4") (name "ADC1_3") (class "Default")
      (node (ref "AP") (pin "38") (pinfunction "(DSR1/MAT1.0/AD1.3)P0.12_38") (pintype "bidirectional"))
      (node (ref "AP_CON_ANALOG1") (pin "7") (pinfunction "S_7") (pintype "passive"))
    )
    (net (code "5") (name "ADC1_4") (class "Default")
      (node (ref "AP") (pin "39") (pinfunction "(DTR1/MAT1.1/AD1.4)P0.13_39") (pintype "bidirectional"))
      (node (ref "AP_CON_ANALOG1") (pin "6") (pinfunction "S_6") (pintype "passive"))
    )
    (net (code "6") (name "ADC1_5") (class "Default")
      (node (ref "AP") (pin "45") (pinfunction "(RI1/EINT2/AD1.5)P0.15_45") (pintype "bidirectional"))
      (node (ref "AP_CON_ANALOG1") (pin "3") (pinfunction "S_3") (pintype "passive"))
    )
    (net (code "7") (name "ADC1_6") (class "Default")
      (node (ref "AP") (pin "1") (pinfunction "(PWM5/AD1.6/CAP1.3)P0.21_1") (pintype "bidirectional"))
      (node (ref "AP_CON_ANALOG1") (pin "4") (pinfunction "S_4") (pintype "passive"))
    )
    (net (code "8") (name "ADC1_7") (class "Default")
      (node (ref "AP") (pin "2") (pinfunction "(AD1.7/CAP0.0/MAT0.0)P0.22_2") (pintype "bidirectional"))
      (node (ref "AP_CON_ANALOG1") (pin "5") (pinfunction "S_5") (pintype "passive"))
    )
    (net (code "9") (name "AP_ADC0_1") (class "Default")
      (node (ref "AP") (pin "13") (pinfunction "(AD0.1/CAP0.2/MAT0.2)P0.28_13") (pintype "bidirectional"))
      (node (ref "AP_CON_ANALOG0") (pin "5") (pinfunction "S_5") (pintype "passive"))
    )
    (net (code "10") (name "AP_ADC0_2") (class "Default")
      (node (ref "AP") (pin "14") (pinfunction "(AD0.2/CAP0.3/MAT0.3)P0.29_14") (pintype "bidirectional"))
      (node (ref "AP_CON_ANALOG0") (pin "4") (pinfunction "S_4") (pintype "passive"))
    )
    (net (code "11") (name "AP_ADC0_3") (class "Default")
      (node (ref "AP") (pin "15") (pinfunction "(AD0.3/EINT3/CAP0.0)P0.30_15") (pintype "bidirectional"))
      (node (ref "AP_CON_ANALOG0") (pin "3") (pinfunction "S_3") (pintype "passive"))
    )
    (net (code "12") (name "AP_AUDIO") (class "Default")
      (node (ref "AP") (pin "9") (pinfunction "(AD0.4/AOUT)P0.25_9") (pintype "bidirectional"))
      (node (ref "AP_CON_ANALOG0") (pin "6") (pinfunction "S_6") (pintype "passive"))
      (node (ref "SJ1") (pin "3") (pinfunction "3_3") (pintype "passive"))
    )
    (net (code "13") (name "AP_I2C_SCL") (class "Default")
      (node (ref "AP") (pin "22") (pinfunction "(SCL0/CAP0.0)P0.2_22") (pintype "bidirectional"))
      (node (ref "AP_CON_I2C") (pin "4") (pinfunction "S_4") (pintype "passive"))
      (node (ref "R2") (pin "1") (pinfunction "1_1") (pintype "passive"))
    )
    (net (code "14") (name "AP_I2C_SDA") (class "Default")
      (node (ref "AP") (pin "26") (pinfunction "(SDA0/MAT0.0/EINT1)P0.3_26") (pintype "bidirectional"))
      (node (ref "AP_CON_I2C") (pin "3") (pinfunction "S_3") (pintype "passive"))
      (node (ref "R3") (pin "1") (pinfunction "1_1") (pintype "passive"))
    )
    (net (code "15") (name "AP_P0.14") (class "Default")
      (node (ref "AP") (pin "41") (pinfunction "(DCD1/EINT1/SDA1)P0.14_41") (pintype "bidirectional"))
      (node (ref "AP_CON_SERIAL") (pin "7") (pinfunction "S_7") (pintype "passive"))
      (node (ref "R27") (pin "1") (pinfunction "1_1") (pintype "passive"))
    )
    (net (code "16") (name "AP_RESET") (class "Default")
      (node (ref "AP") (pin "57") (pinfunction "RESET_57") (pintype "input"))
      (node (ref "AP_CON_SERIAL") (pin "8") (pinfunction "S_8") (pintype "passive"))
      (node (ref "C1") (pin "2") (pinfunction "2_2") (pintype "passive"))
      (node (ref "R1") (pin "1") (pinfunction "1_1") (pintype "passive"))
    )
    (net (code "17") (name "AP_RXD0") (class "Default")
      (node (ref "AP") (pin "21") (pinfunction "(RXD0/PWM3/EINT0)P0.1_21") (pintype "bidirectional"))
      (node (ref "AP_CON_SERIAL") (pin "4") (pinfunction "S_4") (pintype "passive"))
      (node (ref "U$17") (pin "48") (pinfunction "IR_TXD_48") (pintype "bidirectional"))
    )
    (net (code "18") (name "AP_RXD1") (class "Default")
      (node (ref "AP") (pin "34") (pinfunction "(RXD1/PWM6/EINT3)P0.9_34") (pintype "bidirectional"))
      (node (ref "CON_GPS") (pin "4") (pinfunction "S_4") (pintype "passive"))
    )
    (net (code "19") (name "AP_TXD0") (class "Default")
      (node (ref "AP") (pin "19") (pinfunction "(TXD0/PWM1)P0.0_19") (pintype "bidirectional"))
      (node (ref "AP_CON_SERIAL") (pin "3") (pinfunction "S_3") (pintype "passive"))
      (node (ref "U$17") (pin "12") (pinfunction "IR_RXD_12") (pintype "bidirectional"))
    )
    (net (code "20") (name "AP_TXD1") (class "Default")
      (node (ref "AP") (pin "33") (pinfunction "(TXD1/PWM4/AD1.1)P0.8_33") (pintype "bidirectional"))
      (node (ref "CON_GPS") (pin "3") (pinfunction "S_3") (pintype "passive"))
    )
    (net (code "21") (name "AP_USB+") (class "Default")
      (node (ref "AP_CON_SERIAL") (pin "5") (pinfunction "S_5") (pintype "passive"))
      (node (ref "R17") (pin "1") (pinfunction "1_1") (pintype "passive"))
    )
    (net (code "22") (name "AP_USB-") (class "Default")
      (node (ref "AP_CON_SERIAL") (pin "6") (pinfunction "S_6") (pintype "passive"))
      (node (ref "R18") (pin "1") (pinfunction "1_1") (pintype "passive"))
    )
    (net (code "23") (name "AP_USB_CONNECT") (class "Default")
      (node (ref "AP") (pin "17") (pinfunction "(UP_LED/CONNECT)P0.31_17") (pintype "output"))
      (node (ref "Q2") (pin "B") (pinfunction "B_B") (pintype "passive"))
    )
    (net (code "24") (name "AP_USB_N") (class "Default")
      (node (ref "AP") (pin "11") (pinfunction "D-_11") (pintype "bidirectional"))
      (node (ref "C31") (pin "1") (pinfunction "1_1") (pintype "passive"))
      (node (ref "R18") (pin "2") (pinfunction "2_2") (pintype "passive"))
    )
    (net (code "25") (name "AP_USB_P") (class "Default")
      (node (ref "AP") (pin "10") (pinfunction "D+_10") (pintype "bidirectional"))
      (node (ref "C30") (pin "1") (pinfunction "1_1") (pintype "passive"))
      (node (ref "R17") (pin "2") (pinfunction "2_2") (pintype "passive"))
      (node (ref "R19") (pin "2") (pinfunction "2_2") (pintype "passive"))
    )
    (net (code "26") (name "FBW_AD0") (class "Default")
      (node (ref "FBW") (pin "45") (pinfunction "(RI1/EINT2/AD1.5)P0.15_45") (pintype "bidirectional"))
      (node (ref "FBW_CON_ANALOG") (pin "3") (pinfunction "S_3") (pintype "passive"))
    )
    (net (code "27") (name "FBW_AD1") (class "Default")
      (node (ref "FBW") (pin "39") (pinfunction "(DTR1/MAT1.1/AD1.4)P0.13_39") (pintype "bidirectional"))
      (node (ref "FBW_CON_ANALOG") (pin "4") (pinfunction "S_4") (pintype "passive"))
    )
    (net (code "28") (name "FBW_AD2") (class "Default")
      (node (ref "FBW") (pin "38") (pinfunction "(DSR1/MAT1.0/AD1.3)P0.12_38") (pintype "bidirectional"))
      (node (ref "FBW_CON_ANALOG") (pin "5") (pinfunction "S_5") (pintype "passive"))
    )
    (net (code "29") (name "FBW_AD3") (class "Default")
      (node (ref "FBW") (pin "35") (pinfunction "(RTS1/CAP1.0/AD1.2)P0.10_35") (pintype "bidirectional"))
      (node (ref "FBW_CON_ANALOG") (pin "6") (pinfunction "S_6") (pintype "passive"))
    )
    (net (code "30") (name "FBW_AUDIO") (class "Default")
      (node (ref "FBW") (pin "9") (pinfunction "(AD0.4/AOUT)P0.25_9") (pintype "bidirectional"))
      (node (ref "SJ1") (pin "1") (pinfunction "1_1") (pintype "passive"))
    )
    (net (code "31") (name "FBW_I2C_SCL") (class "Default")
      (node (ref "FBW") (pin "22") (pinfunction "(SCL0/CAP0.0)P0.2_22") (pintype "bidirectional"))
      (node (ref "FBW_CON_I2C") (pin "4") (pinfunction "S_4") (pintype "passive"))
      (node (ref "R4") (pin "1") (pinfunction "1_1") (pintype "passive"))
    )
    (net (code "32") (name "FBW_I2C_SDA") (class "Default")
      (node (ref "FBW") (pin "26") (pinfunction "(SDA0/MAT0.0/EINT1)P0.3_26") (pintype "bidirectional"))
      (node (ref "FBW_CON_I2C") (pin "3") (pinfunction "S_3") (pintype "passive"))
      (node (ref "R5") (pin "1") (pinfunction "1_1") (pintype "passive"))
    )
    (net (code "33") (name "FBW_P0.14") (class "Default")
      (node (ref "FBW") (pin "41") (pinfunction "(DCD1/EINT1/SDA1)P0.14_41") (pintype "bidirectional"))
      (node (ref "FBW_CON_SERIAL") (pin "7") (pinfunction "S_7") (pintype "passive"))
      (node (ref "R28") (pin "1") (pinfunction "1_1") (pintype "passive"))
    )
    (net (code "34") (name "FBW_PPM_IN") (class "Default")
      (node (ref "FBW") (pin "30") (pinfunction "(MOSI0/CAP0.2/AD1.0)P0.6_30") (pintype "bidirectional"))
      (node (ref "X1") (pin "3") (pinfunction "S_3") (pintype "passive"))
    )
    (net (code "35") (name "FBW_PWM1") (class "Default")
      (node (ref "FBW") (pin "1") (pinfunction "(PWM5/AD1.6/CAP1.3)P0.21_1") (pintype "bidirectional"))
      (node (ref "FBW_CON_PWM") (pin "3") (pinfunction "S_3") (pintype "passive"))
    )
    (net (code "36") (name "FBW_PWM2") (class "Default")
      (node (ref "FBW") (pin "21") (pinfunction "(RXD0/PWM3/EINT0)P0.1_21") (pintype "bidirectional"))
      (node (ref "FBW_CON_PWM") (pin "4") (pinfunction "S_4") (pintype "passive"))
      (node (ref "FBW_CON_SERIAL") (pin "4") (pinfunction "S_4") (pintype "passive"))
    )
    (net (code "37") (name "FBW_PWM3") (class "Default")
      (node (ref "FBW") (pin "19") (pinfunction "(TXD0/PWM1)P0.0_19") (pintype "bidirectional"))
      (node (ref "FBW_CON_PWM") (pin "5") (pinfunction "S_5") (pintype "passive"))
      (node (ref "FBW_CON_SERIAL") (pin "3") (pinfunction "S_3") (pintype "passive"))
    )
    (net (code "38") (name "FBW_PWM4") (class "Default")
      (node (ref "FBW") (pin "34") (pinfunction "(RXD1/PWM6/EINT3)P0.9_34") (pintype "bidirectional"))
      (node (ref "FBW_CON_PWM") (pin "6") (pinfunction "S_6") (pintype "passive"))
    )
    (net (code "39") (name "FBW_PWM5") (class "Default")
      (node (ref "FBW") (pin "33") (pinfunction "(TXD1/PWM4/AD1.1)P0.8_33") (pintype "bidirectional"))
      (node (ref "FBW_CON_PWM") (pin "7") (pinfunction "S_7") (pintype "passive"))
    )
    (net (code "40") (name "FBW_PWM6") (class "Default")
      (node (ref "FBW") (pin "31") (pinfunction "(SSEL0/PWM2/EINT2)P0.7_31") (pintype "bidirectional"))
      (node (ref "FBW_CON_PWM") (pin "8") (pinfunction "S_8") (pintype "passive"))
    )
    (net (code "41") (name "FBW_RC_RX") (class "Default")
      (node (ref "FBW") (pin "46") (pinfunction "(EINT0/MAT0.2/CAP0.2)P0.16_46") (pintype "bidirectional"))
      (node (ref "FBW_CON_RC") (pin "3") (pinfunction "S_3") (pintype "passive"))
    )
    (net (code "42") (name "FBW_RESET") (class "Default")
      (node (ref "C19") (pin "2") (pinfunction "2_2") (pintype "passive"))
      (node (ref "FBW") (pin "57") (pinfunction "RESET_57") (pintype "input"))
      (node (ref "FBW_CON_SERIAL") (pin "8") (pinfunction "S_8") (pintype "passive"))
      (node (ref "R6") (pin "1") (pinfunction "1_1") (pintype "passive"))
    )
    (net (code "43") (name "FBW_SERVO_CLK") (class "Default")
      (node (ref "FBW") (pin "29") (pinfunction "(MISO0/MAT0.1/A0.7)P0.5_29") (pintype "bidirectional"))
      (node (ref "X1") (pin "4") (pinfunction "S_4") (pintype "passive"))
    )
    (net (code "44") (name "FBW_SERVO_RESET") (class "Default")
      (node (ref "FBW") (pin "28") (pinfunction "P1.25(EXTIN0)_28") (pintype "bidirectional"))
      (node (ref "X1") (pin "5") (pinfunction "S_5") (pintype "passive"))
    )
    (net (code "45") (name "FBW_USB+") (class "Default")
      (node (ref "FBW_CON_SERIAL") (pin "5") (pinfunction "S_5") (pintype "passive"))
      (node (ref "R14") (pin "1") (pinfunction "1_1") (pintype "passive"))
    )
    (net (code "46") (name "FBW_USB-") (class "Default")
      (node (ref "FBW_CON_SERIAL") (pin "6") (pinfunction "S_6") (pintype "passive"))
      (node (ref "R15") (pin "1") (pinfunction "1_1") (pintype "passive"))
    )
    (net (code "47") (name "FBW_USB_CONNECT") (class "Default")
      (node (ref "FBW") (pin "17") (pinfunction "(UP_LED/CONNECT)P0.31_17") (pintype "output"))
      (node (ref "Q1") (pin "B") (pinfunction "B_B") (pintype "passive"))
    )
    (net (code "48") (name "FBW_USB_N") (class "Default")
      (node (ref "C29") (pin "1") (pinfunction "1_1") (pintype "passive"))
      (node (ref "FBW") (pin "11") (pinfunction "D-_11") (pintype "bidirectional"))
      (node (ref "R15") (pin "2") (pinfunction "2_2") (pintype "passive"))
    )
    (net (code "49") (name "FBW_USB_P") (class "Default")
      (node (ref "C28") (pin "1") (pinfunction "1_1") (pintype "passive"))
      (node (ref "FBW") (pin "10") (pinfunction "D+_10") (pintype "bidirectional"))
      (node (ref "R14") (pin "2") (pinfunction "2_2") (pintype "passive"))
      (node (ref "R16") (pin "2") (pinfunction "2_2") (pintype "passive"))
    )
    (net (code "50") (name "GND") (class "Default")
      (node (ref "AP") (pin "18") (pinfunction "VSS_18") (pintype "power_in"))
      (node (ref "AP") (pin "25") (pinfunction "VSS_25") (pintype "power_in"))
      (node (ref "AP") (pin "42") (pinfunction "VSS_42") (pintype "power_in"))
      (node (ref "AP") (pin "50") (pinfunction "VSS_50") (pintype "power_in"))
      (node (ref "AP") (pin "59") (pinfunction "VSSA_59") (pintype "power_in"))
      (node (ref "AP") (pin "6") (pinfunction "VSS_6") (pintype "power_in"))
      (node (ref "AP_CON_ANALOG0") (pin "1") (pinfunction "S_1") (pintype "passive"))
      (node (ref "AP_CON_ANALOG1") (pin "1") (pinfunction "S_1") (pintype "passive"))
      (node (ref "AP_CON_I2C") (pin "1") (pinfunction "S_1") (pintype "passive"))
      (node (ref "AP_CON_SERIAL") (pin "1") (pinfunction "S_1") (pintype "passive"))
      (node (ref "AUDIO") (pin "1") (pinfunction "S_1") (pintype "passive"))
      (node (ref "C1") (pin "1") (pinfunction "1_1") (pintype "passive"))
      (node (ref "C10") (pin "2") (pinfunction "2_2") (pintype "passive"))
      (node (ref "C11") (pin "1") (pinfunction "1_1") (pintype "passive"))
      (node (ref "C12") (pin "1") (pinfunction "1_1") (pintype "passive"))
      (node (ref "C13") (pin "-") (pinfunction "-_-") (pintype "passive"))
      (node (ref "C14") (pin "1") (pinfunction "1_1") (pintype "passive"))
      (node (ref "C15") (pin "2") (pinfunction "2_2") (pintype "passive"))
      (node (ref "C16") (pin "2") (pinfunction "2_2") (pintype "passive"))
      (node (ref "C17") (pin "1") (pinfunction "1_1") (pintype "passive"))
      (node (ref "C18") (pin "-") (pinfunction "-_-") (pintype "passive"))
      (node (ref "C19") (pin "1") (pinfunction "1_1") (pintype "passive"))
      (node (ref "C2") (pin "1") (pinfunction "1_1") (pintype "passive"))
      (node (ref "C20") (pin "1") (pinfunction "1_1") (pintype "passive"))
      (node (ref "C21") (pin "1") (pinfunction "1_1") (pintype "passive"))
      (node (ref "C22") (pin "1") (pinfunction "1_1") (pintype "passive"))
      (node (ref "C23") (pin "2") (pinfunction "2_2") (pintype "passive"))
      (node (ref "C24") (pin "2") (pinfunction "2_2") (pintype "passive"))
      (node (ref "C26") (pin "2") (pinfunction "2_2") (pintype "passive"))
      (node (ref "C28") (pin "2") (pinfunction "2_2") (pintype "passive"))
      (node (ref "C29") (pin "2") (pinfunction "2_2") (pintype "passive"))
      (node (ref "C3") (pin "1") (pinfunction "1_1") (pintype "passive"))
      (node (ref "C30") (pin "2") (pinfunction "2_2") (pintype "passive"))
      (node (ref "C31") (pin "2") (pinfunction "2_2") (pintype "passive"))
      (node (ref "C32") (pin "2") (pinfunction "2_2") (pintype "passive"))
      (node (ref "C33") (pin "2") (pinfunction "2_2") (pintype "passive"))
      (node (ref "C4") (pin "1") (pinfunction "1_1") (pintype "passive"))
      (node (ref "C5") (pin "1") (pinfunction "1_1") (pintype "passive"))
      (node (ref "C6") (pin "1") (pinfunction "1_1") (pintype "passive"))
      (node (ref "C7") (pin "-") (pinfunction "-_-") (pintype "passive"))
      (node (ref "C8") (pin "-") (pinfunction "-_-") (pintype "passive"))
      (node (ref "C9") (pin "1") (pinfunction "1_1") (pintype "passive"))
      (node (ref "CON_GPS") (pin "1") (pinfunction "S_1") (pintype "passive"))
      (node (ref "CON_SPI0") (pin "1") (pinfunction "S_1") (pintype "passive"))
      (node (ref "CON_SPI1") (pin "1") (pinfunction "S_1") (pintype "passive"))
      (node (ref "D1") (pin "1") (pinfunction "C_1") (pintype "passive"))
      (node (ref "FBW") (pin "18") (pinfunction "VSS_18") (pintype "power_in"))
      (node (ref "FBW") (pin "25") (pinfunction "VSS_25") (pintype "power_in"))
      (node (ref "FBW") (pin "42") (pinfunction "VSS_42") (pintype "power_in"))
      (node (ref "FBW") (pin "50") (pinfunction "VSS_50") (pintype "power_in"))
      (node (ref "FBW") (pin "59") (pinfunction "VSSA_59") (pintype "power_in"))
      (node (ref "FBW") (pin "6") (pinfunction "VSS_6") (pintype "power_in"))
      (node (ref "FBW_CON_ANALOG") (pin "1") (pinfunction "S_1") (pintype "passive"))
      (node (ref "FBW_CON_I2C") (pin "1") (pinfunction "S_1") (pintype "passive"))
      (node (ref "FBW_CON_PWM") (pin "1") (pinfunction "S_1") (pintype "passive"))
      (node (ref "FBW_CON_RC") (pin "1") (pinfunction "S_1") (pintype "passive"))
      (node (ref "FBW_CON_SERIAL") (pin "1") (pinfunction "S_1") (pintype "passive"))
      (node (ref "GUM_CON_SERIAL") (pin "1") (pinfunction "S_1") (pintype "passive"))
      (node (ref "IC2") (pin "1") (pinfunction "GND_1") (pintype "power_in"))
      (node (ref "PAD_GND") (pin "1") (pinfunction "P_1") (pintype "passive"))
      (node (ref "R13") (pin "2") (pinfunction "2_2") (pintype "passive"))
      (node (ref "R8") (pin "1") (pinfunction "1_1") (pintype "passive"))
      (node (ref "U$1") (pin "4") (pinfunction "V-_4") (pintype "power_in"))
      (node (ref "U$17") (pin "1") (pinfunction "GND_1") (pintype "power_in"))
      (node (ref "U$17") (pin "31") (pinfunction "GND_31") (pintype "power_in"))
      (node (ref "U$17") (pin "42") (pinfunction "GND_42") (pintype "power_in"))
      (node (ref "U$17") (pin "60") (pinfunction "GND_60") (pintype "power_in"))
      (node (ref "U$17") (pin "7") (pinfunction "GND_7") (pintype "power_in"))
      (node (ref "X1") (pin "1") (pinfunction "S_1") (pintype "passive"))
    )
    (net (code "51") (name "GUM_HW_RXD") (class "Default")
      (node (ref "CON_GPS") (pin "6") (pinfunction "S_6") (pintype "passive"))
      (node (ref "U$17") (pin "33") (pinfunction "X_HW_RXD_33") (pintype "bidirectional"))
    )
    (net (code "52") (name "GUM_HW_TXD") (class "Default")
      (node (ref "CON_GPS") (pin "5") (pinfunction "S_5") (pintype "passive"))
      (node (ref "U$17") (pin "35") (pinfunction "X_HW_TXD_35") (pintype "bidirectional"))
    )
    (net (code "53") (name "GUM_SCL") (class "Default")
      (node (ref "GUM_CON_SERIAL") (pin "8") (pinfunction "S_8") (pintype "passive"))
      (node (ref "R21") (pin "1") (pinfunction "1_1") (pintype "passive"))
      (node (ref "U$17") (pin "20") (pinfunction "X_I2C_SCL_20") (pintype "bidirectional"))
    )
    (net (code "54") (name "GUM_SDA") (class "Default")
      (node (ref "GUM_CON_SERIAL") (pin "7") (pinfunction "S_7") (pintype "passive"))
      (node (ref "R20") (pin "1") (pinfunction "1_1") (pintype "passive"))
      (node (ref "U$17") (pin "19") (pinfunction "X_I2C_SDA_19") (pintype "bidirectional"))
    )
    (net (code "55") (name "GUM_USB+") (class "Default")
      (node (ref "C32") (pin "1") (pinfunction "1_1") (pintype "passive"))
      (node (ref "GUM_CON_SERIAL") (pin "5") (pinfunction "S_5") (pintype "passive"))
      (node (ref "R22") (pin "2") (pinfunction "2_2") (pintype "passive"))
      (node (ref "U$17") (pin "11") (pinfunction "X_USB_P_11") (pintype "bidirectional"))
    )
    (net (code "56") (name "GUM_USB-") (class "Default")
      (node (ref "C33") (pin "1") (pinfunction "1_1") (pintype "passive"))
      (node (ref "GUM_CON_SERIAL") (pin "6") (pinfunction "S_6") (pintype "passive"))
      (node (ref "U$17") (pin "59") (pinfunction "X_USB_N_59") (pintype "bidirectional"))
    )
    (net (code "57") (name "GUM_USB_CONNECT") (class "Default")
      (node (ref "R22") (pin "1") (pinfunction "1_1") (pintype "passive"))
      (node (ref "U$17") (pin "39") (pinfunction "X_RTS_39") (pintype "bidirectional"))
    )
    (net (code "58") (name "GUM_XRXD") (class "Default")
      (node (ref "GUM_CON_SERIAL") (pin "4") (pinfunction "S_4") (pintype "passive"))
      (node (ref "U$17") (pin "54") (pinfunction "X_RXD_54") (pintype "bidirectional"))
    )
    (net (code "59") (name "GUM_XTXD") (class "Default")
      (node (ref "GUM_CON_SERIAL") (pin "3") (pinfunction "S_3") (pintype "passive"))
      (node (ref "U$17") (pin "26") (pinfunction "X_TXD_26") (pintype "bidirectional"))
    )
    (net (code "60") (name "LED1") (class "Default")
      (node (ref "FBW") (pin "32") (pinfunction "P1.24(TRACECLK)_32") (pintype "bidirectional"))
      (node (ref "LED1") (pin "C") (pinfunction "C_C") (pintype "passive"))
    )
    (net (code "61") (name "LED2") (class "Default")
      (node (ref "FBW") (pin "20") (pinfunction "P1.31(/TRST)_20") (pintype "bidirectional"))
      (node (ref "LED2") (pin "C") (pinfunction "C_C") (pintype "passive"))
    )
    (net (code "62") (name "LED3") (class "Default")
      (node (ref "AP") (pin "8") (pinfunction "P1.18(TRACEPKT2)_8") (pintype "bidirectional"))
      (node (ref "LED3") (pin "C") (pinfunction "C_C") (pintype "passive"))
    )
    (net (code "63") (name "LED4") (class "Default")
      (node (ref "AP") (pin "4") (pinfunction "P1.19(TRACEPKT3)_4") (pintype "bidirectional"))
      (node (ref "LED4") (pin "C") (pinfunction "C_C") (pintype "passive"))
    )
    (net (code "64") (name "LPC_CLOCK") (class "Default")
      (node (ref "AP") (pin "62") (pinfunction "XTAL1_62") (pintype "input"))
      (node (ref "C16") (pin "1") (pinfunction "1_1") (pintype "passive"))
      (node (ref "FBW") (pin "61") (pinfunction "XTAL2_61") (pintype "output"))
      (node (ref "U$20") (pin "P$1") (pinfunction "P$1_P$1") (pintype "bidirectional"))
    )
    (net (code "65") (name "Net-(AUDIOC-S)") (class "Default")
      (node (ref "AUDIO") (pin "3") (pinfunction "S_3") (pintype "passive"))
      (node (ref "R12") (pin "2") (pinfunction "2_2") (pintype "passive"))
      (node (ref "R13") (pin "1") (pinfunction "1_1") (pintype "passive"))
    )
    (net (code "66") (name "Net-(C23-Pad1)") (class "Default")
      (node (ref "C23") (pin "1") (pinfunction "1_1") (pintype "passive"))
      (node (ref "R9") (pin "2") (pinfunction "2_2") (pintype "passive"))
      (node (ref "SJ1") (pin "2") (pinfunction "2_2") (pintype "passive"))
    )
    (net (code "67") (name "Net-(C25-Pad1)") (class "Default")
      (node (ref "C25") (pin "1") (pinfunction "1_1") (pintype "passive"))
      (node (ref "R10") (pin "2") (pinfunction "2_2") (pintype "passive"))
      (node (ref "R9") (pin "1") (pinfunction "1_1") (pintype "passive"))
    )
    (net (code "68") (name "Net-(C27-Pad-)") (class "Default")
      (node (ref "C27") (pin "-") (pinfunction "-_-") (pintype "passive"))
      (node (ref "R12") (pin "1") (pinfunction "1_1") (pintype "passive"))
    )
    (net (code "69") (name "Net-(D1-A)") (class "Default")
      (node (ref "D1") (pin "2") (pinfunction "A_2") (pintype "passive"))
      (node (ref "IC1") (pin "1") (pinfunction "GND_1") (pintype "power_in"))
    )
    (net (code "70") (name "Net-(FBW-XTAL1)") (class "Default")
      (node (ref "C15") (pin "1") (pinfunction "1_1") (pintype "passive"))
      (node (ref "FBW") (pin "62") (pinfunction "XTAL1_62") (pintype "input"))
      (node (ref "U$20") (pin "P$3") (pinfunction "P$2_P$3") (pintype "bidirectional"))
    )
    (net (code "71") (name "Net-(LED1-PadA)") (class "Default")
      (node (ref "LED1") (pin "A") (pinfunction "A_A") (pintype "passive"))
      (node (ref "R23") (pin "1") (pinfunction "1_1") (pintype "passive"))
    )
    (net (code "72") (name "Net-(LED2-PadA)") (class "Default")
      (node (ref "LED2") (pin "A") (pinfunction "A_A") (pintype "passive"))
      (node (ref "R24") (pin "1") (pinfunction "1_1") (pintype "passive"))
    )
    (net (code "73") (name "Net-(LED3-PadA)") (class "Default")
      (node (ref "LED3") (pin "A") (pinfunction "A_A") (pintype "passive"))
      (node (ref "R25") (pin "1") (pinfunction "1_1") (pintype "passive"))
    )
    (net (code "74") (name "Net-(LED4-PadA)") (class "Default")
      (node (ref "LED4") (pin "A") (pinfunction "A_A") (pintype "passive"))
      (node (ref "R26") (pin "1") (pinfunction "1_1") (pintype "passive"))
    )
    (net (code "75") (name "Net-(Q1-PadC)") (class "Default")
      (node (ref "Q1") (pin "C") (pinfunction "C_C") (pintype "passive"))
      (node (ref "R16") (pin "1") (pinfunction "1_1") (pintype "passive"))
    )
    (net (code "76") (name "Net-(Q2-PadC)") (class "Default")
      (node (ref "Q2") (pin "C") (pinfunction "C_C") (pintype "passive"))
      (node (ref "R19") (pin "1") (pinfunction "1_1") (pintype "passive"))
    )
    (net (code "77") (name "Net-(U$1A-+IN)") (class "Default")
      (node (ref "C24") (pin "1") (pinfunction "1_1") (pintype "passive"))
      (node (ref "R10") (pin "1") (pinfunction "1_1") (pintype "passive"))
      (node (ref "U$1") (pin "3") (pinfunction "+IN_3") (pintype "input"))
    )
    (net (code "78") (name "Net-(U$1A--IN)") (class "Default")
      (node (ref "C25") (pin "2") (pinfunction "2_2") (pintype "passive"))
      (node (ref "R11") (pin "2") (pinfunction "2_2") (pintype "passive"))
      (node (ref "U$1") (pin "1") (pinfunction "OUT_1") (pintype "output"))
      (node (ref "U$1") (pin "2") (pinfunction "-IN_2") (pintype "input"))
    )
    (net (code "79") (name "Net-(U$1B-+IN)") (class "Default")
      (node (ref "C26") (pin "1") (pinfunction "1_1") (pintype "passive"))
      (node (ref "R11") (pin "1") (pinfunction "1_1") (pintype "passive"))
      (node (ref "U$1") (pin "5") (pinfunction "+IN_5") (pintype "input"))
    )
    (net (code "80") (name "Net-(U$1B--IN)") (class "Default")
      (node (ref "C27") (pin "+") (pinfunction "+_+") (pintype "passive"))
      (node (ref "U$1") (pin "6") (pinfunction "-IN_6") (pintype "input"))
      (node (ref "U$1") (pin "7") (pinfunction "OUT_7") (pintype "output"))
    )
    (net (code "81") (name "SPI0_IT") (class "Default")
      (node (ref "AP") (pin "46") (pinfunction "(EINT0/MAT0.2/CAP0.2)P0.16_46") (pintype "bidirectional"))
      (node (ref "CON_SPI0") (pin "7") (pinfunction "S_7") (pintype "passive"))
    )
    (net (code "82") (name "SPI0_MISO") (class "Default")
      (node (ref "AP") (pin "53") (pinfunction "(CAP1.3/MISO1/MAT1.3)P0.18_53") (pintype "bidirectional"))
      (node (ref "CON_SPI0") (pin "4") (pinfunction "S_4") (pintype "passive"))
      (node (ref "FBW") (pin "53") (pinfunction "(CAP1.3/MISO1/MAT1.3)P0.18_53") (pintype "bidirectional"))
    )
    (net (code "83") (name "SPI0_MOSI") (class "Default")
      (node (ref "AP") (pin "54") (pinfunction "(MAT1.2/MOSI1/CAP1.2)P0.19_54") (pintype "bidirectional"))
      (node (ref "CON_SPI0") (pin "3") (pinfunction "S_3") (pintype "passive"))
      (node (ref "FBW") (pin "54") (pinfunction "(MAT1.2/MOSI1/CAP1.2)P0.19_54") (pintype "bidirectional"))
    )
    (net (code "84") (name "SPI0_SCK") (class "Default")
      (node (ref "AP") (pin "47") (pinfunction "(CAP1.2/SCK1/MAT1.2)P0.17_47") (pintype "bidirectional"))
      (node (ref "CON_SPI0") (pin "5") (pinfunction "S_5") (pintype "passive"))
      (node (ref "FBW") (pin "47") (pinfunction "(CAP1.2/SCK1/MAT1.2)P0.17_47") (pintype "bidirectional"))
    )
    (net (code "85") (name "SPI0_SS") (class "Default")
      (node (ref "AP") (pin "55") (pinfunction "(MAT1.3/SSEL1/EINT3)P0.20_55") (pintype "bidirectional"))
      (node (ref "FBW") (pin "55") (pinfunction "(MAT1.3/SSEL1/EINT3)P0.20_55") (pintype "bidirectional"))
    )
    (net (code "86") (name "SPI0_SS1") (class "Default")
      (node (ref "AP") (pin "48") (pinfunction "P1.20(TRACESYNC)_48") (pintype "bidirectional"))
      (node (ref "CON_SPI0") (pin "6") (pinfunction "S_6") (pintype "passive"))
    )
    (net (code "87") (name "SPI1_IT") (class "Default")
      (node (ref "CON_SPI1") (pin "7") (pinfunction "S_7") (pintype "passive"))
    )
    (net (code "88") (name "SPI1_MISO") (class "Default")
      (node (ref "AP") (pin "29") (pinfunction "(MISO0/MAT0.1/A0.7)P0.5_29") (pintype "bidirectional"))
      (node (ref "CON_SPI1") (pin "4") (pinfunction "S_4") (pintype "passive"))
      (node (ref "U$17") (pin "45") (pinfunction "GPIO_84/NSSP_TRXD_45") (pintype "bidirectional"))
    )
    (net (code "89") (name "SPI1_MOSI") (class "Default")
      (node (ref "AP") (pin "30") (pinfunction "(MOSI0/CAP0.2/AD1.0)P0.6_30") (pintype "bidirectional"))
      (node (ref "CON_SPI1") (pin "3") (pinfunction "S_3") (pintype "passive"))
      (node (ref "U$17") (pin "23") (pinfunction "GPIO_83/NSSP_TRXD_23") (pintype "bidirectional"))
    )
    (net (code "90") (name "SPI1_SCK") (class "Default")
      (node (ref "AP") (pin "27") (pinfunction "(SCK0/CAP0.1/AD0.6)P0.4_27") (pintype "bidirectional"))
      (node (ref "CON_SPI1") (pin "5") (pinfunction "S_5") (pintype "passive"))
      (node (ref "U$17") (pin "21") (pinfunction "GPIO_81/NSSP_CLK_21") (pintype "bidirectional"))
    )
    (net (code "91") (name "SPI1_SS") (class "Default")
      (node (ref "AP") (pin "31") (pinfunction "(SSEL0/PWM2/EINT2)P0.7_31") (pintype "bidirectional"))
      (node (ref "CON_SPI1") (pin "6") (pinfunction "S_6") (pintype "passive"))
      (node (ref "U$17") (pin "44") (pinfunction "GPIO_82/NSSP_FRAME_44") (pintype "bidirectional"))
    )
    (net (code "92") (name "VBAT_IN") (class "Default")
      (node (ref "C18") (pin "+") (pinfunction "+_+") (pintype "passive"))
      (node (ref "C7") (pin "+") (pinfunction "+_+") (pintype "passive"))
      (node (ref "IC1") (pin "3") (pinfunction "VIN_3") (pintype "input"))
      (node (ref "IC2") (pin "3") (pinfunction "VIN_3") (pintype "input"))
      (node (ref "PAD_VIN") (pin "1") (pinfunction "P_1") (pintype "passive"))
      (node (ref "R7") (pin "2") (pinfunction "2_2") (pintype "passive"))
    )
    (net (code "93") (name "VBAT_MEAS") (class "Default")
      (node (ref "C22") (pin "2") (pinfunction "2_2") (pintype "passive"))
      (node (ref "FBW") (pin "27") (pinfunction "(SCK0/CAP0.1/AD0.6)P0.4_27") (pintype "bidirectional"))
      (node (ref "R7") (pin "1") (pinfunction "1_1") (pintype "passive"))
      (node (ref "R8") (pin "2") (pinfunction "2_2") (pintype "passive"))
    )
    (net (code "94") (name "unconnected-(AP-(CTS1{slash}CAP1.1{slash}SCL1)P0.11-Pad37)") (class "Default")
      (node (ref "AP") (pin "37") (pinfunction "(CTS1/CAP1.1/SCL1)P0.11_37") (pintype "bidirectional"))
    )
    (net (code "95") (name "unconnected-(AP-(VBUS)P0.23-Pad58)") (class "Default")
      (node (ref "AP") (pin "58") (pinfunction "(VBUS)P0.23_58") (pintype "bidirectional"))
    )
    (net (code "96") (name "unconnected-(AP-P1.16(TRACEPKT0)-Pad16)") (class "Default")
      (node (ref "AP") (pin "16") (pinfunction "P1.16(TRACEPKT0)_16") (pintype "bidirectional"))
    )
    (net (code "97") (name "unconnected-(AP-P1.17(TRACEPKT1)-Pad12)") (class "Default")
      (node (ref "AP") (pin "12") (pinfunction "P1.17(TRACEPKT1)_12") (pintype "bidirectional"))
    )
    (net (code "98") (name "unconnected-(AP-P1.21(PIPESTAT0)-Pad44)") (class "Default")
      (node (ref "AP") (pin "44") (pinfunction "P1.21(PIPESTAT0)_44") (pintype "bidirectional"))
    )
    (net (code "99") (name "unconnected-(AP-P1.22(PIPESTAT1)-Pad40)") (class "Default")
      (node (ref "AP") (pin "40") (pinfunction "P1.22(PIPESTAT1)_40") (pintype "bidirectional"))
    )
    (net (code "100") (name "unconnected-(AP-P1.23(PIPESTAT2)-Pad36)") (class "Default")
      (node (ref "AP") (pin "36") (pinfunction "P1.23(PIPESTAT2)_36") (pintype "bidirectional"))
    )
    (net (code "101") (name "unconnected-(AP-P1.24(TRACECLK)-Pad32)") (class "Default")
      (node (ref "AP") (pin "32") (pinfunction "P1.24(TRACECLK)_32") (pintype "bidirectional"))
    )
    (net (code "102") (name "unconnected-(AP-P1.25(EXTIN0)-Pad28)") (class "Default")
      (node (ref "AP") (pin "28") (pinfunction "P1.25(EXTIN0)_28") (pintype "bidirectional"))
    )
    (net (code "103") (name "unconnected-(AP-P1.26(RTCK)-Pad24)") (class "Default")
      (node (ref "AP") (pin "24") (pinfunction "P1.26(RTCK)_24") (pintype "bidirectional"))
    )
    (net (code "104") (name "unconnected-(AP-P1.27(TDO)-Pad64)") (class "Default")
      (node (ref "AP") (pin "64") (pinfunction "P1.27(TDO)_64") (pintype "bidirectional"))
    )
    (net (code "105") (name "unconnected-(AP-P1.28(TDI)-Pad60)") (class "Default")
      (node (ref "AP") (pin "60") (pinfunction "P1.28(TDI)_60") (pintype "bidirectional"))
    )
    (net (code "106") (name "unconnected-(AP-P1.29(TCK)-Pad56)") (class "Default")
      (node (ref "AP") (pin "56") (pinfunction "P1.29(TCK)_56") (pintype "bidirectional"))
    )
    (net (code "107") (name "unconnected-(AP-P1.30(TMS)-Pad52)") (class "Default")
      (node (ref "AP") (pin "52") (pinfunction "P1.30(TMS)_52") (pintype "bidirectional"))
    )
    (net (code "108") (name "unconnected-(AP-P1.31({slash}TRST)-Pad20)") (class "Default")
      (node (ref "AP") (pin "20") (pinfunction "P1.31(/TRST)_20") (pintype "bidirectional"))
    )
    (net (code "109") (name "unconnected-(AP-RTXC1-Pad3)") (class "Default")
      (node (ref "AP") (pin "3") (pinfunction "RTXC1_3") (pintype "input"))
    )
    (net (code "110") (name "unconnected-(AP-RTXC2-Pad5)") (class "Default")
      (node (ref "AP") (pin "5") (pinfunction "RTXC2_5") (pintype "output"))
    )
    (net (code "111") (name "unconnected-(AP-XTAL2-Pad61)") (class "Default")
      (node (ref "AP") (pin "61") (pinfunction "XTAL2_61") (pintype "output"))
    )
    (net (code "112") (name "unconnected-(FBW-(AD0.1{slash}CAP0.2{slash}MAT0.2)P0.28-Pad13)") (class "Default")
      (node (ref "FBW") (pin "13") (pinfunction "(AD0.1/CAP0.2/MAT0.2)P0.28_13") (pintype "bidirectional"))
    )
    (net (code "113") (name "unconnected-(FBW-(AD0.2{slash}CAP0.3{slash}MAT0.3)P0.29-Pad14)") (class "Default")
      (node (ref "FBW") (pin "14") (pinfunction "(AD0.2/CAP0.3/MAT0.3)P0.29_14") (pintype "bidirectional"))
    )
    (net (code "114") (name "unconnected-(FBW-(AD0.3{slash}EINT3{slash}CAP0.0)P0.30-Pad15)") (class "Default")
      (node (ref "FBW") (pin "15") (pinfunction "(AD0.3/EINT3/CAP0.0)P0.30_15") (pintype "bidirectional"))
    )
    (net (code "115") (name "unconnected-(FBW-(AD1.7{slash}CAP0.0{slash}MAT0.0)P0.22-Pad2)") (class "Default")
      (node (ref "FBW") (pin "2") (pinfunction "(AD1.7/CAP0.0/MAT0.0)P0.22_2") (pintype "bidirectional"))
    )
    (net (code "116") (name "unconnected-(FBW-(CTS1{slash}CAP1.1{slash}SCL1)P0.11-Pad37)") (class "Default")
      (node (ref "FBW") (pin "37") (pinfunction "(CTS1/CAP1.1/SCL1)P0.11_37") (pintype "bidirectional"))
    )
    (net (code "117") (name "unconnected-(FBW-(VBUS)P0.23-Pad58)") (class "Default")
      (node (ref "FBW") (pin "58") (pinfunction "(VBUS)P0.23_58") (pintype "bidirectional"))
    )
    (net (code "118") (name "unconnected-(FBW-P1.16(TRACEPKT0)-Pad16)") (class "Default")
      (node (ref "FBW") (pin "16") (pinfunction "P1.16(TRACEPKT0)_16") (pintype "bidirectional"))
    )
    (net (code "119") (name "unconnected-(FBW-P1.17(TRACEPKT1)-Pad12)") (class "Default")
      (node (ref "FBW") (pin "12") (pinfunction "P1.17(TRACEPKT1)_12") (pintype "bidirectional"))
    )
    (net (code "120") (name "unconnected-(FBW-P1.18(TRACEPKT2)-Pad8)") (class "Default")
      (node (ref "FBW") (pin "8") (pinfunction "P1.18(TRACEPKT2)_8") (pintype "bidirectional"))
    )
    (net (code "121") (name "unconnected-(FBW-P1.19(TRACEPKT3)-Pad4)") (class "Default")
      (node (ref "FBW") (pin "4") (pinfunction "P1.19(TRACEPKT3)_4") (pintype "bidirectional"))
    )
    (net (code "122") (name "unconnected-(FBW-P1.20(TRACESYNC)-Pad48)") (class "Default")
      (node (ref "FBW") (pin "48") (pinfunction "P1.20(TRACESYNC)_48") (pintype "bidirectional"))
    )
    (net (code "123") (name "unconnected-(FBW-P1.21(PIPESTAT0)-Pad44)") (class "Default")
      (node (ref "FBW") (pin "44") (pinfunction "P1.21(PIPESTAT0)_44") (pintype "bidirectional"))
    )
    (net (code "124") (name "unconnected-(FBW-P1.22(PIPESTAT1)-Pad40)") (class "Default")
      (node (ref "FBW") (pin "40") (pinfunction "P1.22(PIPESTAT1)_40") (pintype "bidirectional"))
    )
    (net (code "125") (name "unconnected-(FBW-P1.23(PIPESTAT2)-Pad36)") (class "Default")
      (node (ref "FBW") (pin "36") (pinfunction "P1.23(PIPESTAT2)_36") (pintype "bidirectional"))
    )
    (net (code "126") (name "unconnected-(FBW-P1.26(RTCK)-Pad24)") (class "Default")
      (node (ref "FBW") (pin "24") (pinfunction "P1.26(RTCK)_24") (pintype "bidirectional"))
    )
    (net (code "127") (name "unconnected-(FBW-P1.27(TDO)-Pad64)") (class "Default")
      (node (ref "FBW") (pin "64") (pinfunction "P1.27(TDO)_64") (pintype "bidirectional"))
    )
    (net (code "128") (name "unconnected-(FBW-P1.28(TDI)-Pad60)") (class "Default")
      (node (ref "FBW") (pin "60") (pinfunction "P1.28(TDI)_60") (pintype "bidirectional"))
    )
    (net (code "129") (name "unconnected-(FBW-P1.29(TCK)-Pad56)") (class "Default")
      (node (ref "FBW") (pin "56") (pinfunction "P1.29(TCK)_56") (pintype "bidirectional"))
    )
    (net (code "130") (name "unconnected-(FBW-P1.30(TMS)-Pad52)") (class "Default")
      (node (ref "FBW") (pin "52") (pinfunction "P1.30(TMS)_52") (pintype "bidirectional"))
    )
    (net (code "131") (name "unconnected-(FBW-RTXC1-Pad3)") (class "Default")
      (node (ref "FBW") (pin "3") (pinfunction "RTXC1_3") (pintype "input"))
    )
    (net (code "132") (name "unconnected-(FBW-RTXC2-Pad5)") (class "Default")
      (node (ref "FBW") (pin "5") (pinfunction "RTXC2_5") (pintype "output"))
    )
    (net (code "133") (name "unconnected-(U$17-BITCLK-Pad58)") (class "Default")
      (node (ref "U$17") (pin "58") (pinfunction "BITCLK_58") (pintype "bidirectional"))
    )
    (net (code "134") (name "unconnected-(U$17-L_BIAS-Pad3)") (class "Default")
      (node (ref "U$17") (pin "3") (pinfunction "L_BIAS_3") (pintype "bidirectional"))
    )
    (net (code "135") (name "unconnected-(U$17-L_DD00-Pad18)") (class "Default")
      (node (ref "U$17") (pin "18") (pinfunction "L_DD00_18") (pintype "bidirectional"))
    )
    (net (code "136") (name "unconnected-(U$17-L_DD01-Pad50)") (class "Default")
      (node (ref "U$17") (pin "50") (pinfunction "L_DD01_50") (pintype "bidirectional"))
    )
    (net (code "137") (name "unconnected-(U$17-L_DD02-Pad13)") (class "Default")
      (node (ref "U$17") (pin "13") (pinfunction "L_DD02_13") (pintype "bidirectional"))
    )
    (net (code "138") (name "unconnected-(U$17-L_DD03-Pad4)") (class "Default")
      (node (ref "U$17") (pin "4") (pinfunction "L_DD03_4") (pintype "bidirectional"))
    )
    (net (code "139") (name "unconnected-(U$17-L_DD04-Pad47)") (class "Default")
      (node (ref "U$17") (pin "47") (pinfunction "L_DD04_47") (pintype "bidirectional"))
    )
    (net (code "140") (name "unconnected-(U$17-L_DD05-Pad52)") (class "Default")
      (node (ref "U$17") (pin "52") (pinfunction "L_DD05_52") (pintype "bidirectional"))
    )
    (net (code "141") (name "unconnected-(U$17-L_DD06-Pad40)") (class "Default")
      (node (ref "U$17") (pin "40") (pinfunction "L_DD06_40") (pintype "bidirectional"))
    )
    (net (code "142") (name "unconnected-(U$17-L_DD07-Pad53)") (class "Default")
      (node (ref "U$17") (pin "53") (pinfunction "L_DD07_53") (pintype "bidirectional"))
    )
    (net (code "143") (name "unconnected-(U$17-L_DD08-Pad6)") (class "Default")
      (node (ref "U$17") (pin "6") (pinfunction "L_DD08_6") (pintype "bidirectional"))
    )
    (net (code "144") (name "unconnected-(U$17-L_DD09-Pad2)") (class "Default")
      (node (ref "U$17") (pin "2") (pinfunction "L_DD09_2") (pintype "bidirectional"))
    )
    (net (code "145") (name "unconnected-(U$17-L_DD10-Pad51)") (class "Default")
      (node (ref "U$17") (pin "51") (pinfunction "L_DD10_51") (pintype "bidirectional"))
    )
    (net (code "146") (name "unconnected-(U$17-L_DD11-Pad10)") (class "Default")
      (node (ref "U$17") (pin "10") (pinfunction "L_DD11_10") (pintype "bidirectional"))
    )
    (net (code "147") (name "unconnected-(U$17-L_DD12-Pad9)") (class "Default")
      (node (ref "U$17") (pin "9") (pinfunction "L_DD12_9") (pintype "bidirectional"))
    )
    (net (code "148") (name "unconnected-(U$17-L_DD13-Pad8)") (class "Default")
      (node (ref "U$17") (pin "8") (pinfunction "L_DD13_8") (pintype "bidirectional"))
    )
    (net (code "149") (name "unconnected-(U$17-L_DD14-Pad55)") (class "Default")
      (node (ref "U$17") (pin "55") (pinfunction "L_DD14_55") (pintype "bidirectional"))
    )
    (net (code "150") (name "unconnected-(U$17-L_DD15-Pad56)") (class "Default")
      (node (ref "U$17") (pin "56") (pinfunction "L_DD15_56") (pintype "bidirectional"))
    )
    (net (code "151") (name "unconnected-(U$17-L_FCLK-Pad41)") (class "Default")
      (node (ref "U$17") (pin "41") (pinfunction "L_FCLK_41") (pintype "bidirectional"))
    )
    (net (code "152") (name "unconnected-(U$17-L_LCLK-Pad16)") (class "Default")
      (node (ref "U$17") (pin "16") (pinfunction "L_LCLK_16") (pintype "bidirectional"))
    )
    (net (code "153") (name "unconnected-(U$17-L_PCLK-Pad57)") (class "Default")
      (node (ref "U$17") (pin "57") (pinfunction "L_PCLK_57") (pintype "bidirectional"))
    )
    (net (code "154") (name "unconnected-(U$17-NACRESET-Pad49)") (class "Default")
      (node (ref "U$17") (pin "49") (pinfunction "NACRESET_49") (pintype "bidirectional"))
    )
    (net (code "155") (name "unconnected-(U$17-NRESET-Pad37)") (class "Default")
      (node (ref "U$17") (pin "37") (pinfunction "NRESET_37") (pintype "bidirectional"))
    )
    (net (code "156") (name "unconnected-(U$17-NTRST-Pad38)") (class "Default")
      (node (ref "U$17") (pin "38") (pinfunction "NTRST_38") (pintype "bidirectional"))
    )
    (net (code "157") (name "unconnected-(U$17-SDATA_IN0-Pad43)") (class "Default")
      (node (ref "U$17") (pin "43") (pinfunction "SDATA_IN0_43") (pintype "bidirectional"))
    )
    (net (code "158") (name "unconnected-(U$17-SDATA_IN1-Pad15)") (class "Default")
      (node (ref "U$17") (pin "15") (pinfunction "SDATA_IN1_15") (pintype "bidirectional"))
    )
    (net (code "159") (name "unconnected-(U$17-SDATA_OUT-Pad5)") (class "Default")
      (node (ref "U$17") (pin "5") (pinfunction "SDATA_OUT_5") (pintype "bidirectional"))
    )
    (net (code "160") (name "unconnected-(U$17-SYNC-Pad46)") (class "Default")
      (node (ref "U$17") (pin "46") (pinfunction "SYNC_46") (pintype "bidirectional"))
    )
    (net (code "161") (name "unconnected-(U$17-TCK-Pad27)") (class "Default")
      (node (ref "U$17") (pin "27") (pinfunction "TCK_27") (pintype "bidirectional"))
    )
    (net (code "162") (name "unconnected-(U$17-TDI-Pad24)") (class "Default")
      (node (ref "U$17") (pin "24") (pinfunction "TDI_24") (pintype "bidirectional"))
    )
    (net (code "163") (name "unconnected-(U$17-TDO-Pad22)") (class "Default")
      (node (ref "U$17") (pin "22") (pinfunction "TDO_22") (pintype "bidirectional"))
    )
    (net (code "164") (name "unconnected-(U$17-TMS-Pad25)") (class "Default")
      (node (ref "U$17") (pin "25") (pinfunction "TMS_25") (pintype "bidirectional"))
    )
    (net (code "165") (name "unconnected-(U$17-X_CTS-Pad14)") (class "Default")
      (node (ref "U$17") (pin "14") (pinfunction "X_CTS_14") (pintype "bidirectional"))
    )
    (net (code "166") (name "unconnected-(U$17-X_HW_CTS-Pad32)") (class "Default")
      (node (ref "U$17") (pin "32") (pinfunction "X_HW_CTS_32") (pintype "bidirectional"))
    )
    (net (code "167") (name "unconnected-(U$17-X_HW_RTS-Pad34)") (class "Default")
      (node (ref "U$17") (pin "34") (pinfunction "X_HW_RTS_34") (pintype "bidirectional"))
    )
    (net (code "168") (name "unconnected-(U$17-X_PWM0-Pad36)") (class "Default")
      (node (ref "U$17") (pin "36") (pinfunction "X_PWM0_36") (pintype "bidirectional"))
    )
    (net (code "169") (name "unconnected-(U$17-X_PWM1-Pad17)") (class "Default")
      (node (ref "U$17") (pin "17") (pinfunction "X_PWM1_17") (pintype "bidirectional"))
    )
  )
)
